# XMICRO-BP8.net
KiCad netlist of a schematic drawn in EAGLE
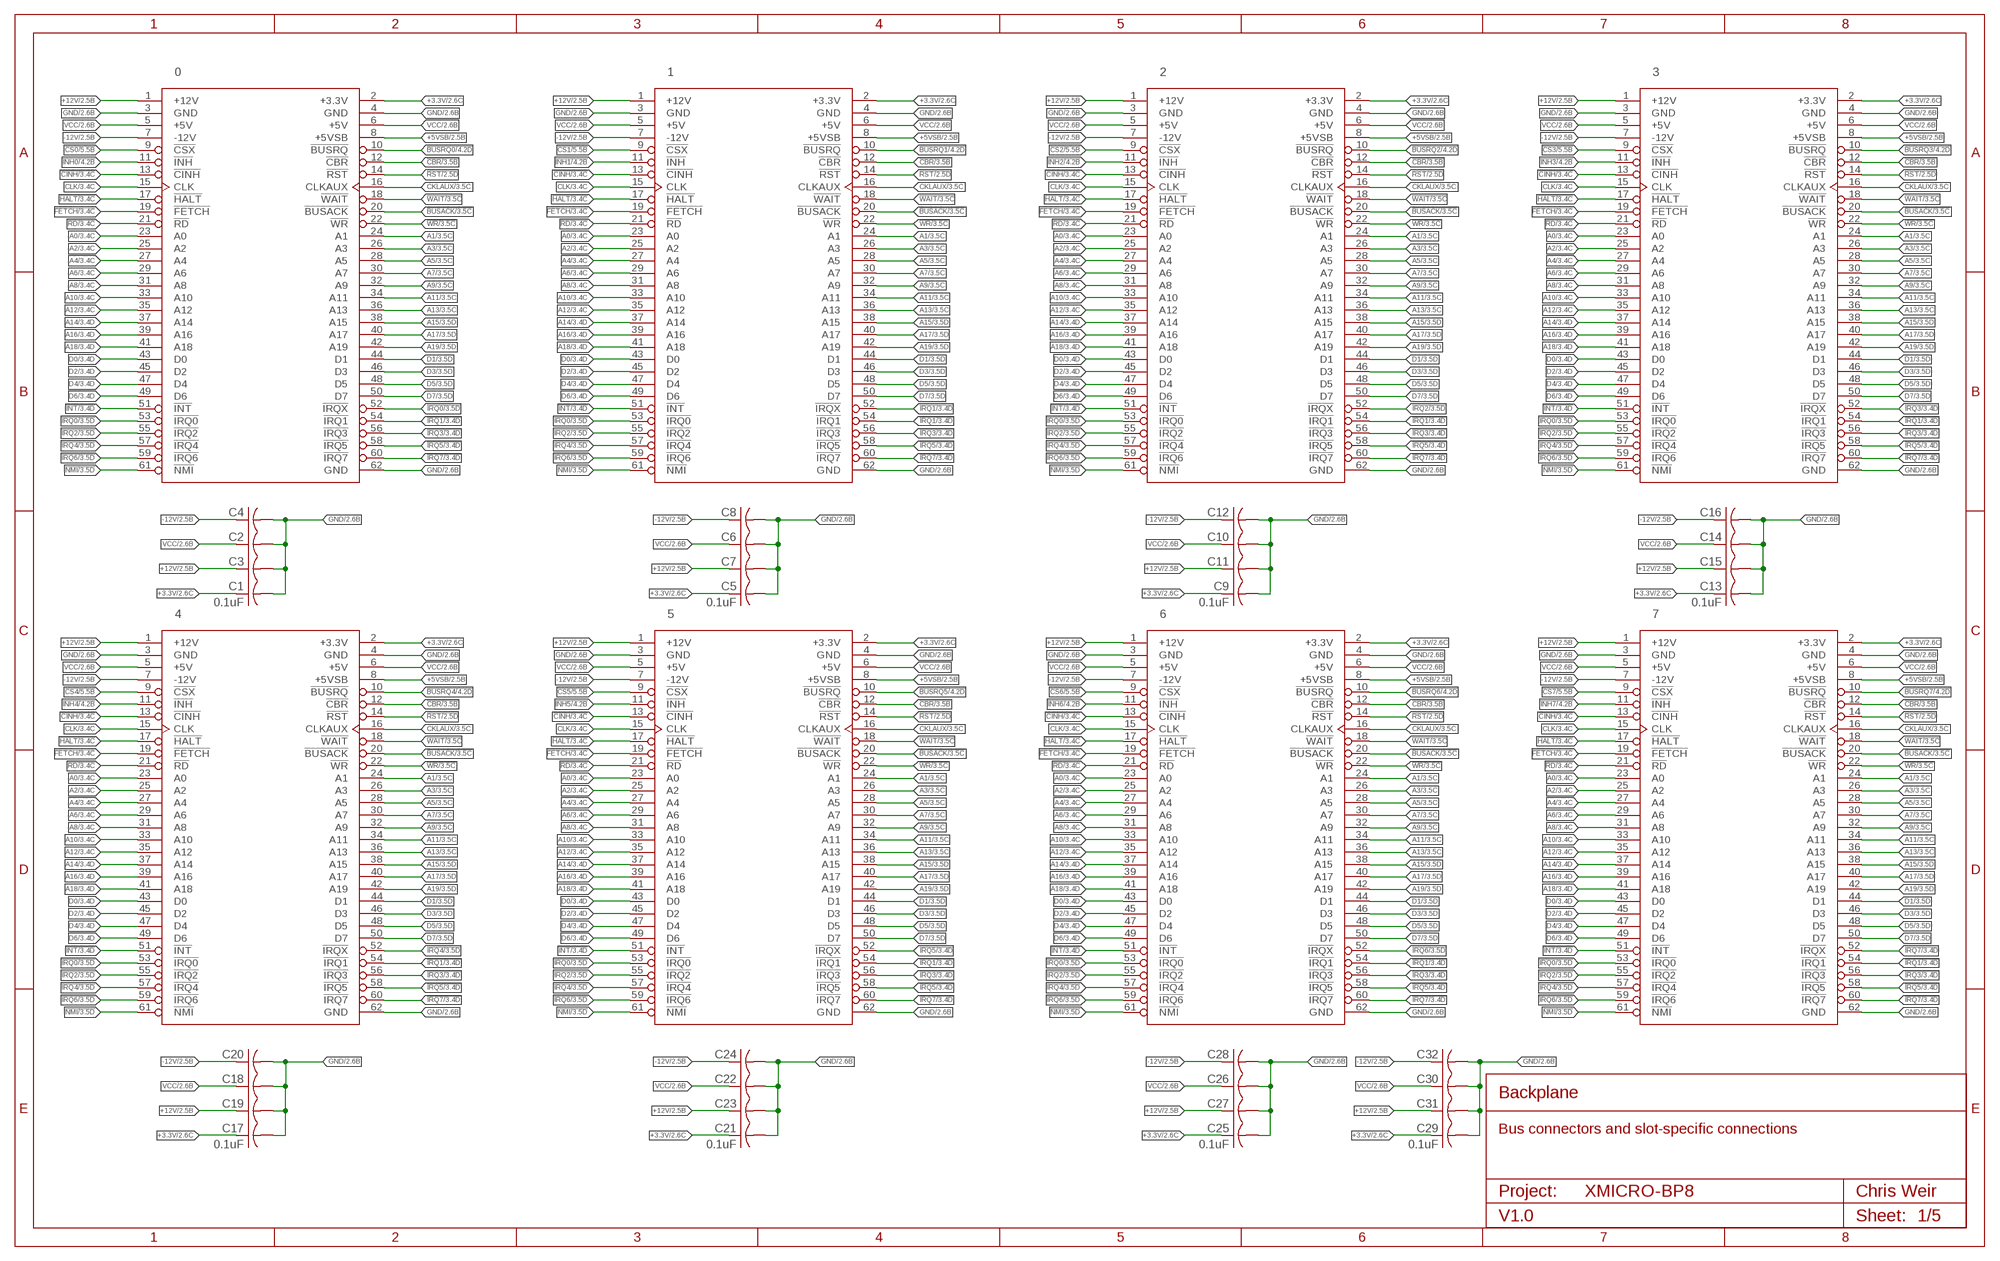
[diagram p0: schematic, sheet 1]
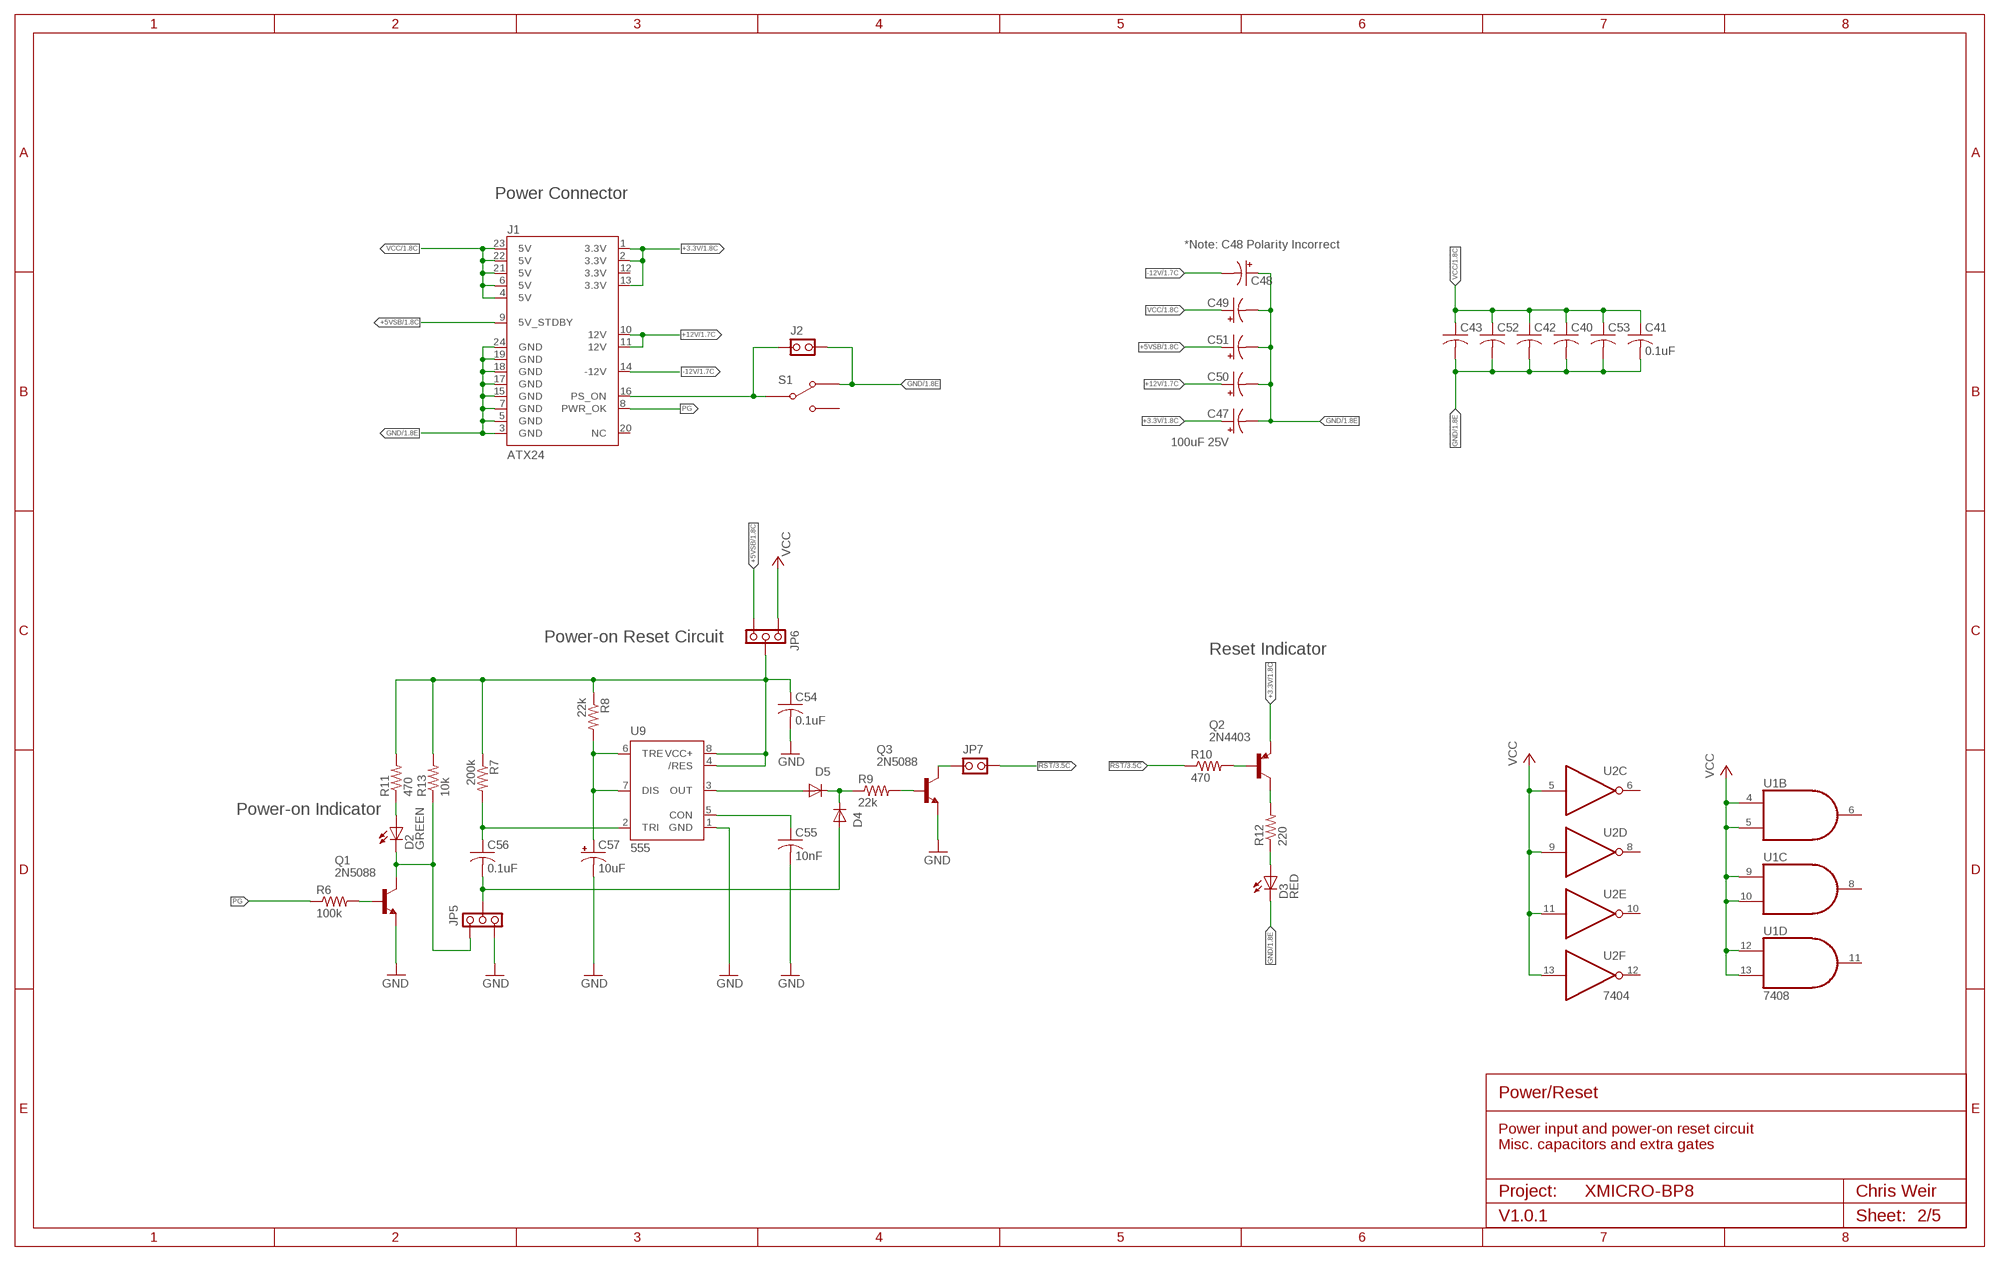
[diagram p1: schematic, sheet 2]
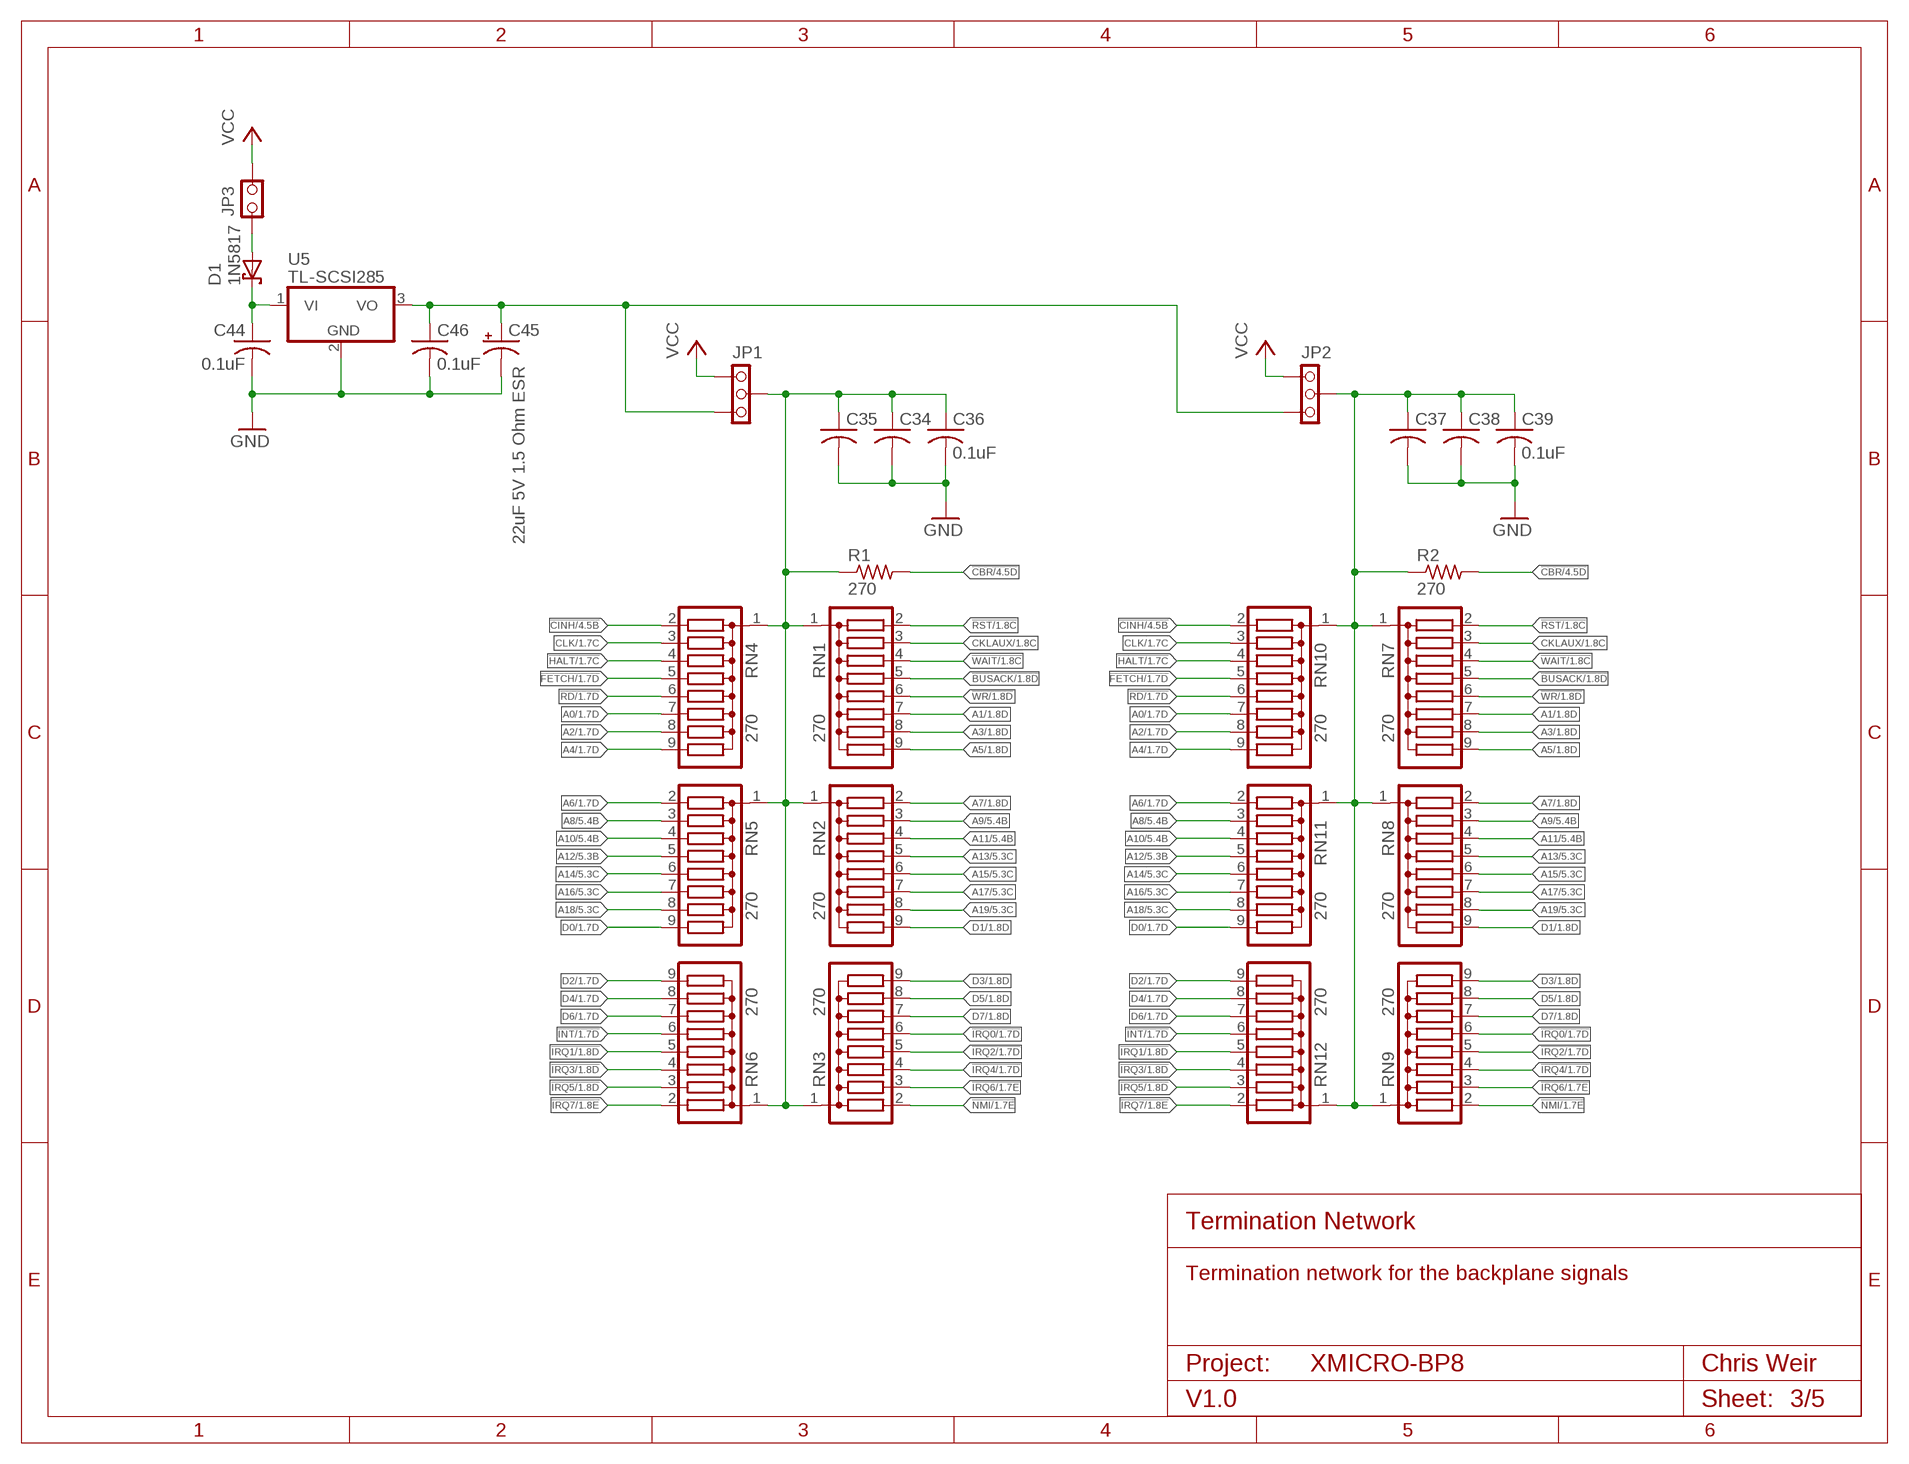
[diagram p2: schematic, sheet 3]
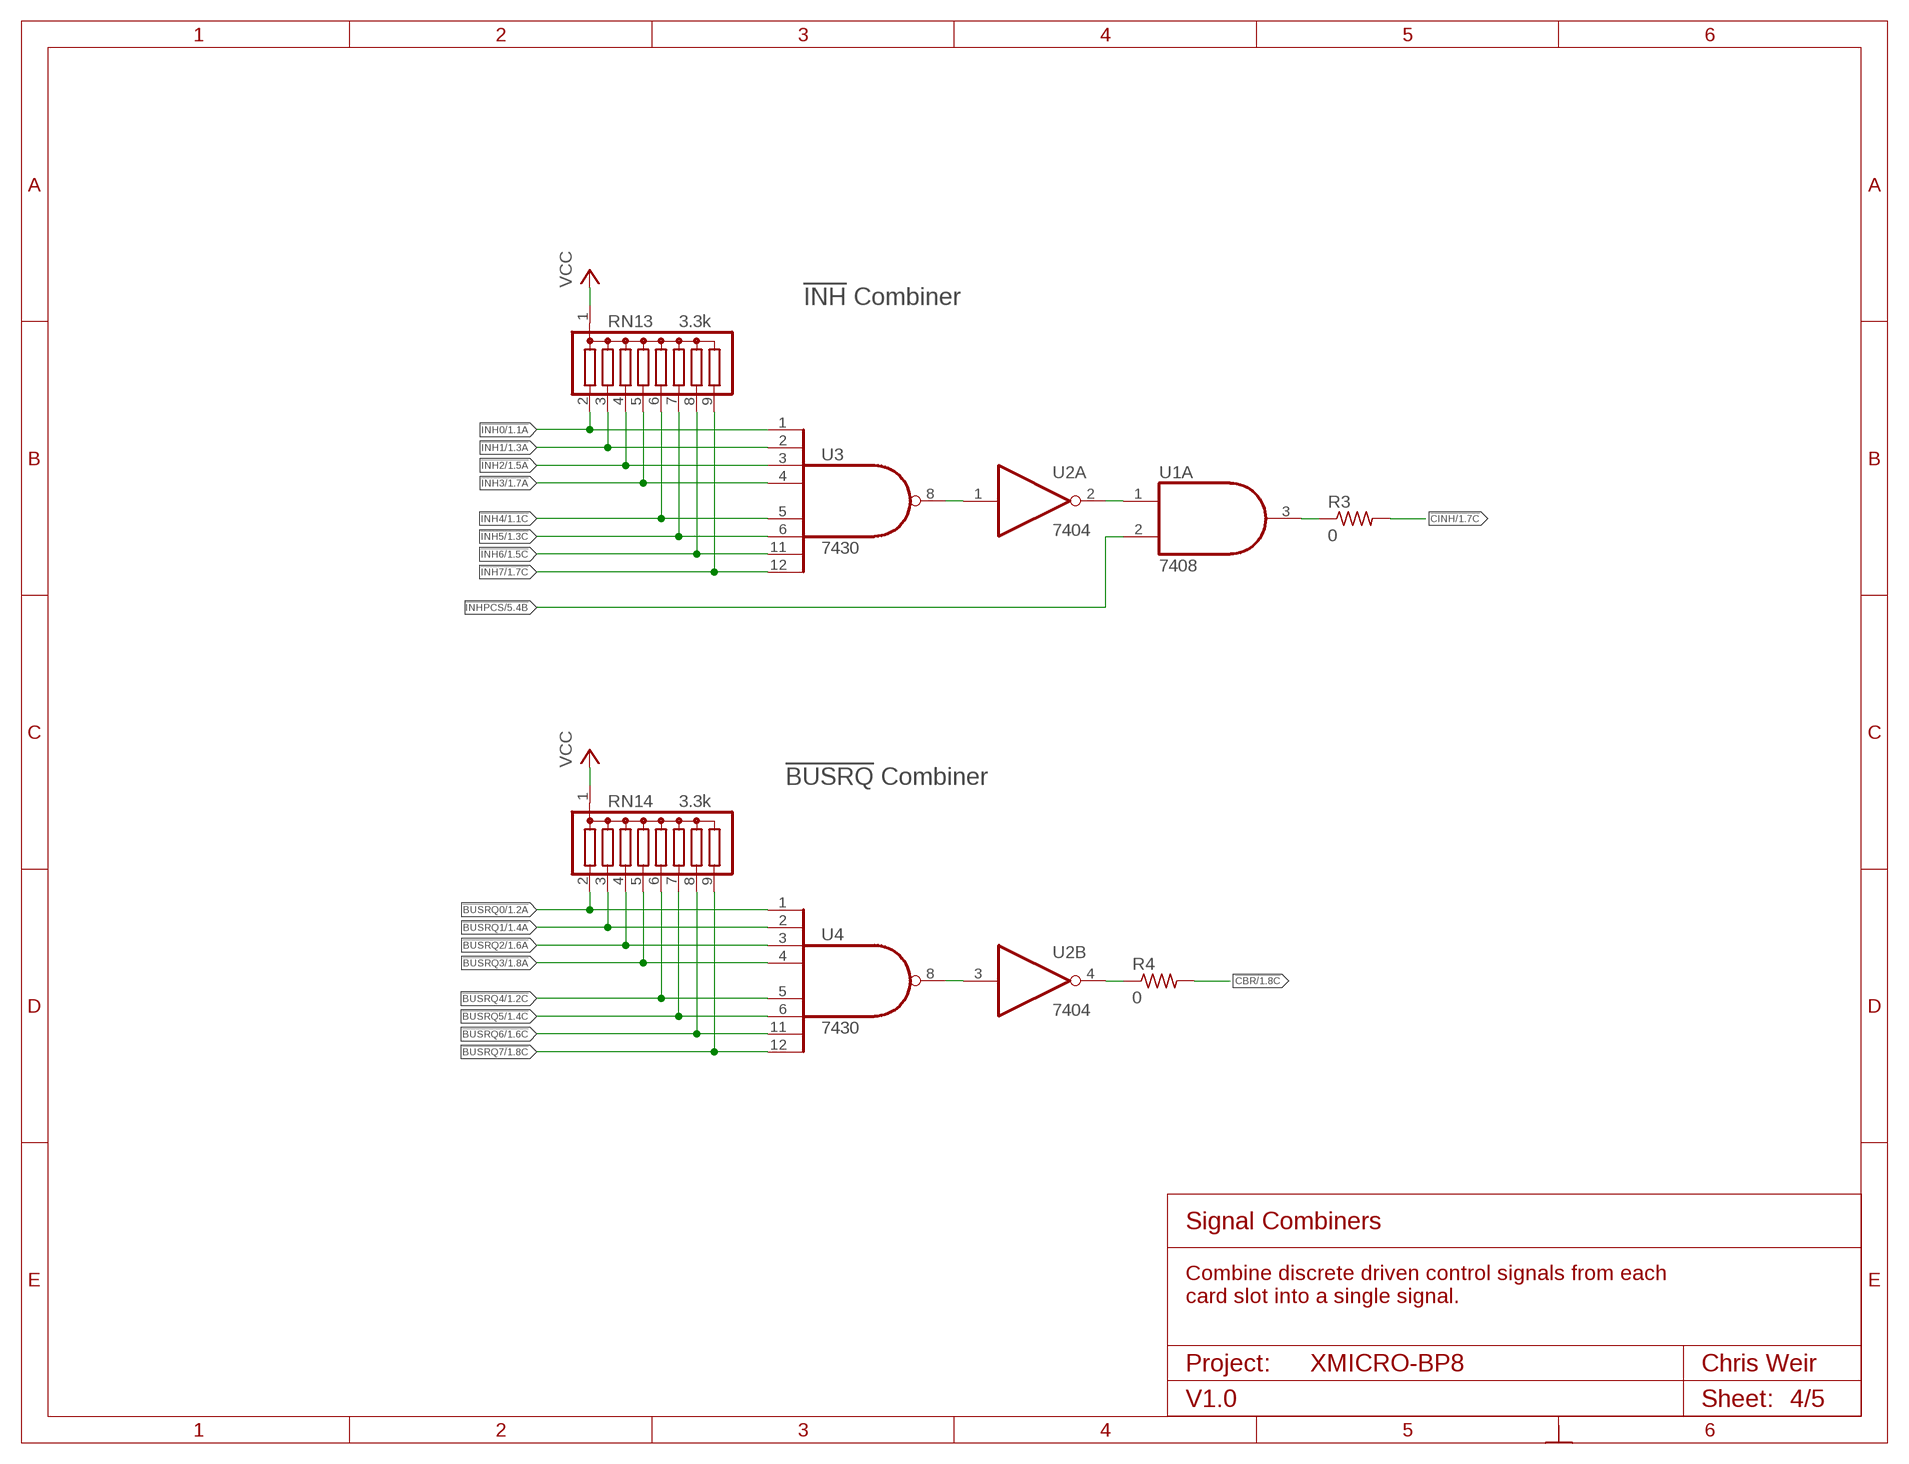
[diagram p3: schematic, sheet 4]
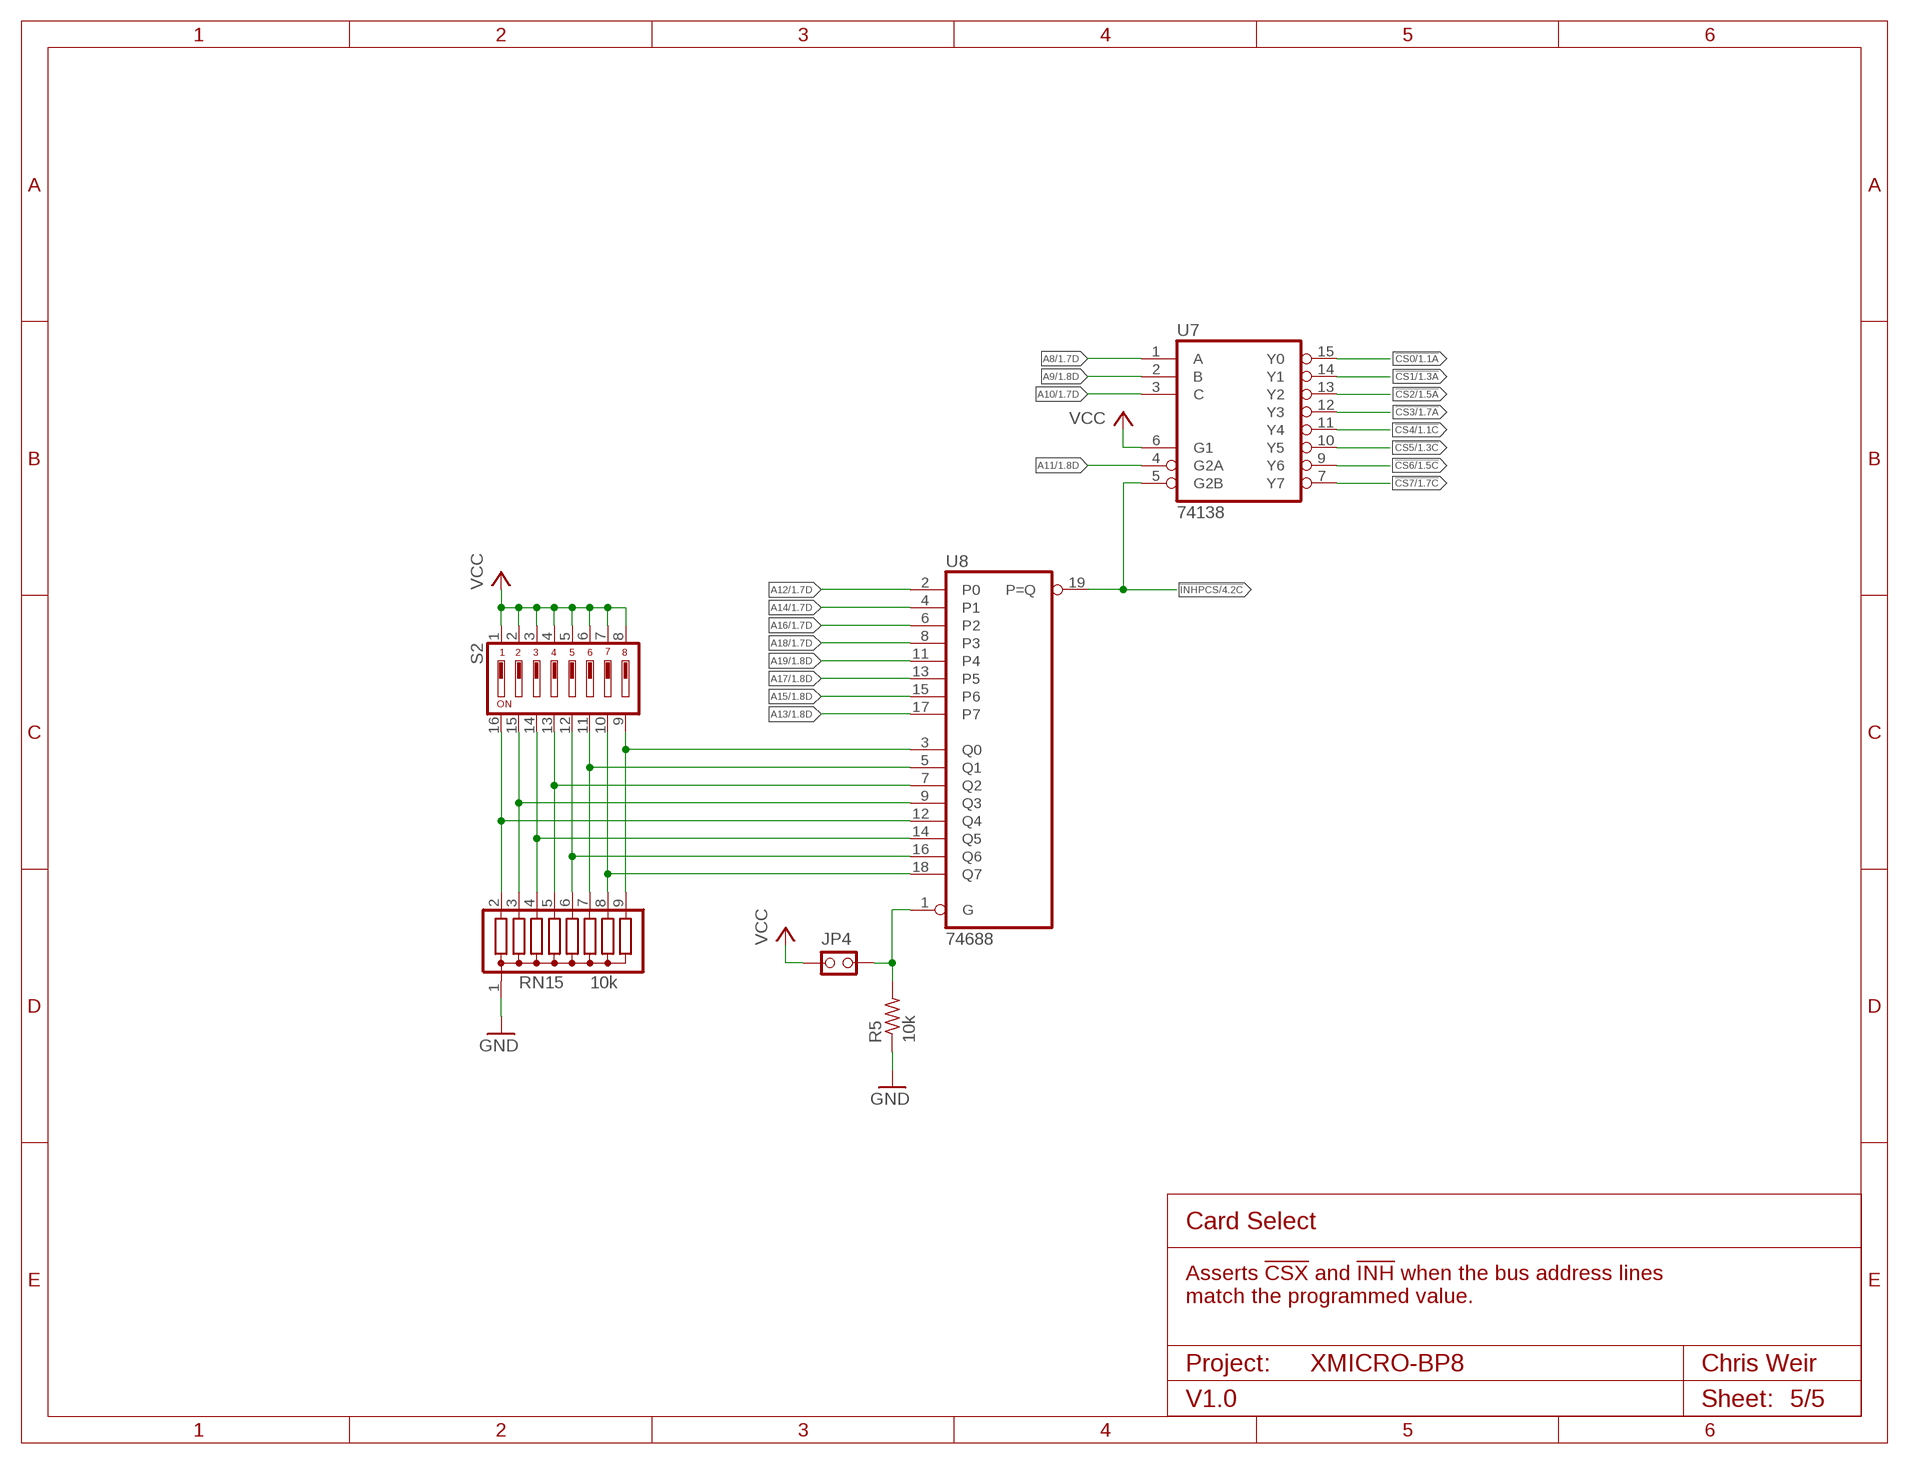
[diagram p4: schematic, sheet 5]

(export (version "E")
  (design (tool "Eeschema 10.0.6"))
  (components
    (comp (ref "C34")
      (value "0.1uF")
      (footprint "eagle-import:C025-024X044")
      (libsource (lib "eagle-import") (part "C-US025-024X044"))
    )
    (comp (ref "C35")
      (value "0.1uF")
      (footprint "eagle-import:C025-024X044")
      (libsource (lib "eagle-import") (part "C-US025-024X044"))
    )
    (comp (ref "C36")
      (value "0.1uF")
      (footprint "eagle-import:C025-024X044")
      (libsource (lib "eagle-import") (part "C-US025-024X044"))
    )
    (comp (ref "C37")
      (value "0.1uF")
      (footprint "eagle-import:C025-024X044")
      (libsource (lib "eagle-import") (part "C-US025-024X044"))
    )
    (comp (ref "C38")
      (value "0.1uF")
      (footprint "eagle-import:C025-024X044")
      (libsource (lib "eagle-import") (part "C-US025-024X044"))
    )
    (comp (ref "C39")
      (value "0.1uF")
      (footprint "eagle-import:C025-024X044")
      (libsource (lib "eagle-import") (part "C-US025-024X044"))
    )
    (comp (ref "C44")
      (value "0.1uF")
      (footprint "eagle-import:C025-024X044")
      (libsource (lib "eagle-import") (part "C-US025-024X044"))
    )
    (comp (ref "C45")
      (value "22uF 5V 1.5 Ohm ESR")
      (footprint "eagle-import:E2,5-7")
      (libsource (lib "eagle-import") (part "CPOL-USE2.5-7"))
    )
    (comp (ref "C46")
      (value "0.1uF")
      (footprint "eagle-import:C050-024X044")
      (libsource (lib "eagle-import") (part "C-US050-024X044"))
    )
    (comp (ref "D1")
      (value "1N5817")
      (footprint "eagle-import:DO41-7.6")
      (libsource (lib "eagle-import") (part "1N5817-B"))
    )
    (comp (ref "JP1")
      (value "PINHD1X3THRU")
      (footprint "eagle-import:1X03")
      (libsource (lib "eagle-import") (part "PINHD1X3THRU"))
    )
    (comp (ref "JP2")
      (value "PINHD1X3THRU")
      (footprint "eagle-import:1X03")
      (libsource (lib "eagle-import") (part "PINHD1X3THRU"))
    )
    (comp (ref "JP3")
      (value "PINHD-1X2THRU")
      (footprint "eagle-import:1X02")
      (libsource (lib "eagle-import") (part "PINHD-1X2THRU"))
    )
    (comp (ref "R1")
      (value "270")
      (footprint "eagle-import:0207_10")
      (libsource (lib "eagle-import") (part "R-US_0207/10"))
    )
    (comp (ref "R2")
      (value "270")
      (footprint "eagle-import:0207_10")
      (libsource (lib "eagle-import") (part "R-US_0207/10"))
    )
    (comp (ref "RN1")
      (value "270")
      (footprint "eagle-import:SIL9")
      (fields (field (name "OC_FARNELL") "unknown") (field (name "OC_NEWARK") "unknown"))
      (libsource (lib "eagle-import") (part "G08R"))
    )
    (comp (ref "RN2")
      (value "270")
      (footprint "eagle-import:SIL9")
      (fields (field (name "OC_FARNELL") "unknown") (field (name "OC_NEWARK") "unknown"))
      (libsource (lib "eagle-import") (part "G08R"))
    )
    (comp (ref "RN3")
      (value "270")
      (footprint "eagle-import:SIL9")
      (fields (field (name "OC_FARNELL") "unknown") (field (name "OC_NEWARK") "unknown"))
      (libsource (lib "eagle-import") (part "G08R"))
    )
    (comp (ref "RN4")
      (value "270")
      (footprint "eagle-import:SIL9")
      (fields (field (name "OC_FARNELL") "unknown") (field (name "OC_NEWARK") "unknown"))
      (libsource (lib "eagle-import") (part "G08R"))
    )
    (comp (ref "RN5")
      (value "270")
      (footprint "eagle-import:SIL9")
      (fields (field (name "OC_FARNELL") "unknown") (field (name "OC_NEWARK") "unknown"))
      (libsource (lib "eagle-import") (part "G08R"))
    )
    (comp (ref "RN6")
      (value "270")
      (footprint "eagle-import:SIL9")
      (fields (field (name "OC_FARNELL") "unknown") (field (name "OC_NEWARK") "unknown"))
      (libsource (lib "eagle-import") (part "G08R"))
    )
    (comp (ref "RN7")
      (value "270")
      (footprint "eagle-import:SIL9")
      (fields (field (name "OC_FARNELL") "unknown") (field (name "OC_NEWARK") "unknown"))
      (libsource (lib "eagle-import") (part "G08R"))
    )
    (comp (ref "RN8")
      (value "270")
      (footprint "eagle-import:SIL9")
      (fields (field (name "OC_FARNELL") "unknown") (field (name "OC_NEWARK") "unknown"))
      (libsource (lib "eagle-import") (part "G08R"))
    )
    (comp (ref "RN9")
      (value "270")
      (footprint "eagle-import:SIL9")
      (fields (field (name "OC_FARNELL") "unknown") (field (name "OC_NEWARK") "unknown"))
      (libsource (lib "eagle-import") (part "G08R"))
    )
    (comp (ref "RN10")
      (value "270")
      (footprint "eagle-import:SIL9")
      (fields (field (name "OC_FARNELL") "unknown") (field (name "OC_NEWARK") "unknown"))
      (libsource (lib "eagle-import") (part "G08R"))
    )
    (comp (ref "RN11")
      (value "270")
      (footprint "eagle-import:SIL9")
      (fields (field (name "OC_FARNELL") "unknown") (field (name "OC_NEWARK") "unknown"))
      (libsource (lib "eagle-import") (part "G08R"))
    )
    (comp (ref "RN12")
      (value "270")
      (footprint "eagle-import:SIL9")
      (fields (field (name "OC_FARNELL") "unknown") (field (name "OC_NEWARK") "unknown"))
      (libsource (lib "eagle-import") (part "G08R"))
    )
    (comp (ref "U5")
      (value "TL-SCSI285")
      (footprint "eagle-import:TO220H")
      (libsource (lib "eagle-import") (part "TL-SCSI285-TO220H"))
    )
    (comp (ref "JP4")
      (value "PINHD-1X2THRU")
      (footprint "eagle-import:1X02")
      (libsource (lib "eagle-import") (part "PINHD-1X2THRU"))
    )
    (comp (ref "R5")
      (value "10k")
      (footprint "eagle-import:0207_10")
      (libsource (lib "eagle-import") (part "R-US_0207/10"))
    )
    (comp (ref "RN15")
      (value "10k")
      (footprint "eagle-import:SIL9")
      (fields (field (name "OC_FARNELL") "unknown") (field (name "OC_NEWARK") "unknown"))
      (libsource (lib "eagle-import") (part "G08R"))
    )
    (comp (ref "S2")
      (value "SW-DIP08")
      (footprint "eagle-import:SW-DIP8")
      (libsource (lib "eagle-import") (part "SW-DIP08"))
    )
    (comp (ref "U7")
      (value "74138")
      (footprint "eagle-import:DIL16")
      (libsource (lib "eagle-import") (part "74138NLS"))
    )
    (comp (ref "U8")
      (value "74688")
      (footprint "eagle-import:DIL20")
      (libsource (lib "eagle-import") (part "74688NLS"))
    )
    (comp (ref "C40")
      (value "0.1uF")
      (footprint "eagle-import:C025-024X044")
      (libsource (lib "eagle-import") (part "C-US025-024X044"))
    )
    (comp (ref "C41")
      (value "0.1uF")
      (footprint "eagle-import:C025-024X044")
      (libsource (lib "eagle-import") (part "C-US025-024X044"))
    )
    (comp (ref "C42")
      (value "0.1uF")
      (footprint "eagle-import:C025-024X044")
      (libsource (lib "eagle-import") (part "C-US025-024X044"))
    )
    (comp (ref "C43")
      (value "0.1uF")
      (footprint "eagle-import:C025-024X044")
      (libsource (lib "eagle-import") (part "C-US025-024X044"))
    )
    (comp (ref "C47")
      (value "100uF 25V")
      (footprint "eagle-import:C-10-5")
      (libsource (lib "eagle-import") (part "CPOL-US-10-5"))
    )
    (comp (ref "C48")
      (value "220uF 10V")
      (footprint "eagle-import:C-10-5")
      (libsource (lib "eagle-import") (part "CPOL-US-10-5"))
    )
    (comp (ref "C49")
      (value "220uF 10V")
      (footprint "eagle-import:C-10-5")
      (libsource (lib "eagle-import") (part "CPOL-US-10-5"))
    )
    (comp (ref "C50")
      (value "100uF 25V")
      (footprint "eagle-import:C-10-5")
      (libsource (lib "eagle-import") (part "CPOL-US-10-5"))
    )
    (comp (ref "C51")
      (value "220uF 10V")
      (footprint "eagle-import:C-10-5")
      (libsource (lib "eagle-import") (part "CPOL-US-10-5"))
    )
    (comp (ref "C52")
      (value "0.1uF")
      (footprint "eagle-import:C025-024X044")
      (libsource (lib "eagle-import") (part "C-US025-024X044"))
    )
    (comp (ref "C53")
      (value "0.1uF")
      (footprint "eagle-import:C025-024X044")
      (libsource (lib "eagle-import") (part "C-US025-024X044"))
    )
    (comp (ref "C54")
      (value "0.1uF")
      (footprint "eagle-import:C025-024X044")
      (libsource (lib "eagle-import") (part "C-US025-024X044"))
    )
    (comp (ref "C55")
      (value "10nF")
      (footprint "eagle-import:C025-024X044")
      (libsource (lib "eagle-import") (part "C-US025-024X044"))
    )
    (comp (ref "C56")
      (value "0.1uF")
      (footprint "eagle-import:C025-024X044")
      (libsource (lib "eagle-import") (part "C-US025-024X044"))
    )
    (comp (ref "C57")
      (value "10uF")
      (footprint "eagle-import:E2,5-7")
      (libsource (lib "eagle-import") (part "CPOL-USE2.5-7"))
    )
    (comp (ref "D2")
      (value "GREEN")
      (footprint "eagle-import:LED5MM")
      (libsource (lib "eagle-import") (part "LED5MM"))
    )
    (comp (ref "D3")
      (value "RED")
      (footprint "eagle-import:LED5MM")
      (libsource (lib "eagle-import") (part "LED5MM"))
    )
    (comp (ref "D4")
      (value "1N4148DO35-7")
      (footprint "eagle-import:DO35-7")
      (libsource (lib "eagle-import") (part "1N4148DO35-7"))
    )
    (comp (ref "D5")
      (value "1N4148DO35-7")
      (footprint "eagle-import:DO35-7")
      (libsource (lib "eagle-import") (part "1N4148DO35-7"))
    )
    (comp (ref "J1")
      (value "ATX24")
      (footprint "eagle-import:ATX24")
      (libsource (lib "eagle-import") (part "ATX24"))
    )
    (comp (ref "J2")
      (value "PINHD-1X2THRU")
      (footprint "eagle-import:1X02")
      (libsource (lib "eagle-import") (part "PINHD-1X2THRU"))
    )
    (comp (ref "JP5")
      (value "PINHD1X3THRU")
      (footprint "eagle-import:1X03")
      (libsource (lib "eagle-import") (part "PINHD1X3THRU"))
    )
    (comp (ref "JP6")
      (value "PINHD1X3THRU")
      (footprint "eagle-import:1X03")
      (libsource (lib "eagle-import") (part "PINHD1X3THRU"))
    )
    (comp (ref "JP7")
      (value "PINHD-1X2THRU")
      (footprint "eagle-import:1X02")
      (libsource (lib "eagle-import") (part "PINHD-1X2THRU"))
    )
    (comp (ref "Q1")
      (value "2N5088")
      (footprint "eagle-import:TO92")
      (libsource (lib "eagle-import") (part "TRANSISTOR-NPN-2N5088"))
    )
    (comp (ref "Q2")
      (value "2N4403")
      (footprint "eagle-import:TO92")
      (libsource (lib "eagle-import") (part "TRANSISTOR-PNP-2N4403"))
    )
    (comp (ref "Q3")
      (value "2N5088")
      (footprint "eagle-import:TO92")
      (libsource (lib "eagle-import") (part "TRANSISTOR-NPN-2N5088"))
    )
    (comp (ref "R6")
      (value "100k")
      (footprint "eagle-import:0207_10")
      (libsource (lib "eagle-import") (part "R-US_0207/10"))
    )
    (comp (ref "R7")
      (value "200k")
      (footprint "eagle-import:0207_10")
      (libsource (lib "eagle-import") (part "R-US_0207/10"))
    )
    (comp (ref "R8")
      (value "22k")
      (footprint "eagle-import:0207_10")
      (libsource (lib "eagle-import") (part "R-US_0207/10"))
    )
    (comp (ref "R9")
      (value "22k")
      (footprint "eagle-import:0207_10")
      (libsource (lib "eagle-import") (part "R-US_0207/10"))
    )
    (comp (ref "R10")
      (value "470")
      (footprint "eagle-import:0207_10")
      (libsource (lib "eagle-import") (part "R-US_0207/10"))
    )
    (comp (ref "R11")
      (value "470")
      (footprint "eagle-import:0207_10")
      (libsource (lib "eagle-import") (part "R-US_0207/10"))
    )
    (comp (ref "R12")
      (value "220")
      (footprint "eagle-import:0207_10")
      (libsource (lib "eagle-import") (part "R-US_0207/10"))
    )
    (comp (ref "R13")
      (value "10k")
      (footprint "eagle-import:0207_10")
      (libsource (lib "eagle-import") (part "R-US_0207/10"))
    )
    (comp (ref "S1")
      (value "SPDTT411013")
      (footprint "eagle-import:T411013")
      (libsource (lib "eagle-import") (part "SPDTT411013"))
    )
    (comp (ref "U1")
      (value "7408")
      (footprint "eagle-import:DIL14")
      (libsource (lib "eagle-import") (part "7408NLS"))
    )
    (comp (ref "U2")
      (value "7404")
      (footprint "eagle-import:DIL14")
      (libsource (lib "eagle-import") (part "7404NLS"))
    )
    (comp (ref "U9")
      (value "555")
      (footprint "eagle-import:DIL-08")
      (fields (field (name "MF") "Arrow Electronics") (field (name "MPN") "NE555N"))
      (libsource (lib "eagle-import") (part "NE555"))
    )
    (comp (ref "0")
      (value "XMICRO-BUS-PHYSICAL-EDGE62F")
      (footprint "eagle-import:EDGE62F")
      (libsource (lib "eagle-import") (part "XMICRO-BUS-PHYSICAL-EDGE62F"))
    )
    (comp (ref "1")
      (value "XMICRO-BUS-PHYSICAL-EDGE62F")
      (footprint "eagle-import:EDGE62F")
      (libsource (lib "eagle-import") (part "XMICRO-BUS-PHYSICAL-EDGE62F"))
    )
    (comp (ref "2")
      (value "XMICRO-BUS-PHYSICAL-EDGE62F")
      (footprint "eagle-import:EDGE62F")
      (libsource (lib "eagle-import") (part "XMICRO-BUS-PHYSICAL-EDGE62F"))
    )
    (comp (ref "3")
      (value "XMICRO-BUS-PHYSICAL-EDGE62F")
      (footprint "eagle-import:EDGE62F")
      (libsource (lib "eagle-import") (part "XMICRO-BUS-PHYSICAL-EDGE62F"))
    )
    (comp (ref "4")
      (value "XMICRO-BUS-PHYSICAL-EDGE62F")
      (footprint "eagle-import:EDGE62F")
      (libsource (lib "eagle-import") (part "XMICRO-BUS-PHYSICAL-EDGE62F"))
    )
    (comp (ref "5")
      (value "XMICRO-BUS-PHYSICAL-EDGE62F")
      (footprint "eagle-import:EDGE62F")
      (libsource (lib "eagle-import") (part "XMICRO-BUS-PHYSICAL-EDGE62F"))
    )
    (comp (ref "6")
      (value "XMICRO-BUS-PHYSICAL-EDGE62F")
      (footprint "eagle-import:EDGE62F")
      (libsource (lib "eagle-import") (part "XMICRO-BUS-PHYSICAL-EDGE62F"))
    )
    (comp (ref "7")
      (value "XMICRO-BUS-PHYSICAL-EDGE62F")
      (footprint "eagle-import:EDGE62F")
      (libsource (lib "eagle-import") (part "XMICRO-BUS-PHYSICAL-EDGE62F"))
    )
    (comp (ref "C1")
      (value "0.1uF")
      (footprint "eagle-import:C025-024X044")
      (libsource (lib "eagle-import") (part "C-US025-024X044"))
    )
    (comp (ref "C2")
      (value "0.1uF")
      (footprint "eagle-import:C025-024X044")
      (libsource (lib "eagle-import") (part "C-US025-024X044"))
    )
    (comp (ref "C3")
      (value "0.1uF")
      (footprint "eagle-import:C025-024X044")
      (libsource (lib "eagle-import") (part "C-US025-024X044"))
    )
    (comp (ref "C4")
      (value "0.1uF")
      (footprint "eagle-import:C050-024X044")
      (libsource (lib "eagle-import") (part "C-US050-024X044"))
    )
    (comp (ref "C5")
      (value "0.1uF")
      (footprint "eagle-import:C025-024X044")
      (libsource (lib "eagle-import") (part "C-US025-024X044"))
    )
    (comp (ref "C6")
      (value "0.1uF")
      (footprint "eagle-import:C025-024X044")
      (libsource (lib "eagle-import") (part "C-US025-024X044"))
    )
    (comp (ref "C7")
      (value "0.1uF")
      (footprint "eagle-import:C025-024X044")
      (libsource (lib "eagle-import") (part "C-US025-024X044"))
    )
    (comp (ref "C8")
      (value "0.1uF")
      (footprint "eagle-import:C050-024X044")
      (libsource (lib "eagle-import") (part "C-US050-024X044"))
    )
    (comp (ref "C9")
      (value "0.1uF")
      (footprint "eagle-import:C025-024X044")
      (libsource (lib "eagle-import") (part "C-US025-024X044"))
    )
    (comp (ref "C10")
      (value "0.1uF")
      (footprint "eagle-import:C025-024X044")
      (libsource (lib "eagle-import") (part "C-US025-024X044"))
    )
    (comp (ref "C11")
      (value "0.1uF")
      (footprint "eagle-import:C025-024X044")
      (libsource (lib "eagle-import") (part "C-US025-024X044"))
    )
    (comp (ref "C12")
      (value "0.1uF")
      (footprint "eagle-import:C050-024X044")
      (libsource (lib "eagle-import") (part "C-US050-024X044"))
    )
    (comp (ref "C13")
      (value "0.1uF")
      (footprint "eagle-import:C025-024X044")
      (libsource (lib "eagle-import") (part "C-US025-024X044"))
    )
    (comp (ref "C14")
      (value "0.1uF")
      (footprint "eagle-import:C025-024X044")
      (libsource (lib "eagle-import") (part "C-US025-024X044"))
    )
    (comp (ref "C15")
      (value "0.1uF")
      (footprint "eagle-import:C025-024X044")
      (libsource (lib "eagle-import") (part "C-US025-024X044"))
    )
    (comp (ref "C16")
      (value "0.1uF")
      (footprint "eagle-import:C050-024X044")
      (libsource (lib "eagle-import") (part "C-US050-024X044"))
    )
    (comp (ref "C17")
      (value "0.1uF")
      (footprint "eagle-import:C025-024X044")
      (libsource (lib "eagle-import") (part "C-US025-024X044"))
    )
    (comp (ref "C18")
      (value "0.1uF")
      (footprint "eagle-import:C025-024X044")
      (libsource (lib "eagle-import") (part "C-US025-024X044"))
    )
    (comp (ref "C19")
      (value "0.1uF")
      (footprint "eagle-import:C025-024X044")
      (libsource (lib "eagle-import") (part "C-US025-024X044"))
    )
    (comp (ref "C20")
      (value "0.1uF")
      (footprint "eagle-import:C050-024X044")
      (libsource (lib "eagle-import") (part "C-US050-024X044"))
    )
    (comp (ref "C21")
      (value "0.1uF")
      (footprint "eagle-import:C025-024X044")
      (libsource (lib "eagle-import") (part "C-US025-024X044"))
    )
    (comp (ref "C22")
      (value "0.1uF")
      (footprint "eagle-import:C025-024X044")
      (libsource (lib "eagle-import") (part "C-US025-024X044"))
    )
    (comp (ref "C23")
      (value "0.1uF")
      (footprint "eagle-import:C025-024X044")
      (libsource (lib "eagle-import") (part "C-US025-024X044"))
    )
    (comp (ref "C24")
      (value "0.1uF")
      (footprint "eagle-import:C050-024X044")
      (libsource (lib "eagle-import") (part "C-US050-024X044"))
    )
    (comp (ref "C25")
      (value "0.1uF")
      (footprint "eagle-import:C025-024X044")
      (libsource (lib "eagle-import") (part "C-US025-024X044"))
    )
    (comp (ref "C26")
      (value "0.1uF")
      (footprint "eagle-import:C025-024X044")
      (libsource (lib "eagle-import") (part "C-US025-024X044"))
    )
    (comp (ref "C27")
      (value "0.1uF")
      (footprint "eagle-import:C025-024X044")
      (libsource (lib "eagle-import") (part "C-US025-024X044"))
    )
    (comp (ref "C28")
      (value "0.1uF")
      (footprint "eagle-import:C050-024X044")
      (libsource (lib "eagle-import") (part "C-US050-024X044"))
    )
    (comp (ref "C29")
      (value "0.1uF")
      (footprint "eagle-import:C025-024X044")
      (libsource (lib "eagle-import") (part "C-US025-024X044"))
    )
    (comp (ref "C30")
      (value "0.1uF")
      (footprint "eagle-import:C025-024X044")
      (libsource (lib "eagle-import") (part "C-US025-024X044"))
    )
    (comp (ref "C31")
      (value "0.1uF")
      (footprint "eagle-import:C025-024X044")
      (libsource (lib "eagle-import") (part "C-US025-024X044"))
    )
    (comp (ref "C32")
      (value "0.1uF")
      (footprint "eagle-import:C025-024X044")
      (libsource (lib "eagle-import") (part "C-US025-024X044"))
    )
    (comp (ref "R3")
      (value "0")
      (footprint "eagle-import:0207_10")
      (libsource (lib "eagle-import") (part "R-US_0207/10"))
    )
    (comp (ref "R4")
      (value "0")
      (footprint "eagle-import:0207_10")
      (libsource (lib "eagle-import") (part "R-US_0207/10"))
    )
    (comp (ref "RN13")
      (value "3.3k")
      (footprint "eagle-import:SIL9")
      (fields (field (name "OC_FARNELL") "unknown") (field (name "OC_NEWARK") "unknown"))
      (libsource (lib "eagle-import") (part "G08R"))
    )
    (comp (ref "RN14")
      (value "3.3k")
      (footprint "eagle-import:SIL9")
      (fields (field (name "OC_FARNELL") "unknown") (field (name "OC_NEWARK") "unknown"))
      (libsource (lib "eagle-import") (part "G08R"))
    )
    (comp (ref "U3")
      (value "7430")
      (footprint "eagle-import:DIL14")
      (libsource (lib "eagle-import") (part "7430NLS"))
    )
    (comp (ref "U4")
      (value "7430")
      (footprint "eagle-import:DIL14")
      (libsource (lib "eagle-import") (part "7430NLS"))
    )
  )
  (nets
    (net (code "1") (name "+3.3V") (class "Default")
      (node (ref "0") (pin "2") (pinfunction "+3.3V_2") (pintype "bidirectional"))
      (node (ref "1") (pin "2") (pinfunction "+3.3V_2") (pintype "bidirectional"))
      (node (ref "2") (pin "2") (pinfunction "+3.3V_2") (pintype "bidirectional"))
      (node (ref "3") (pin "2") (pinfunction "+3.3V_2") (pintype "bidirectional"))
      (node (ref "4") (pin "2") (pinfunction "+3.3V_2") (pintype "bidirectional"))
      (node (ref "5") (pin "2") (pinfunction "+3.3V_2") (pintype "bidirectional"))
      (node (ref "6") (pin "2") (pinfunction "+3.3V_2") (pintype "bidirectional"))
      (node (ref "7") (pin "2") (pinfunction "+3.3V_2") (pintype "bidirectional"))
      (node (ref "C1") (pin "1") (pinfunction "1_1") (pintype "passive"))
      (node (ref "C13") (pin "1") (pinfunction "1_1") (pintype "passive"))
      (node (ref "C17") (pin "1") (pinfunction "1_1") (pintype "passive"))
      (node (ref "C21") (pin "1") (pinfunction "1_1") (pintype "passive"))
      (node (ref "C25") (pin "1") (pinfunction "1_1") (pintype "passive"))
      (node (ref "C29") (pin "1") (pinfunction "1_1") (pintype "passive"))
      (node (ref "C47") (pin "+") (pinfunction "+_+") (pintype "passive"))
      (node (ref "C5") (pin "1") (pinfunction "1_1") (pintype "passive"))
      (node (ref "C9") (pin "1") (pinfunction "1_1") (pintype "passive"))
      (node (ref "J1") (pin "1") (pinfunction "3.3V_1") (pintype "bidirectional"))
      (node (ref "J1") (pin "13") (pinfunction "3.3V_13") (pintype "bidirectional"))
      (node (ref "J1") (pin "2") (pinfunction "3.3V_2") (pintype "bidirectional"))
      (node (ref "Q2") (pin "1") (pinfunction "E_1") (pintype "passive"))
    )
    (net (code "2") (name "+5VSB") (class "Default")
      (node (ref "0") (pin "8") (pinfunction "+5VSB_8") (pintype "bidirectional"))
      (node (ref "1") (pin "8") (pinfunction "+5VSB_8") (pintype "bidirectional"))
      (node (ref "2") (pin "8") (pinfunction "+5VSB_8") (pintype "bidirectional"))
      (node (ref "3") (pin "8") (pinfunction "+5VSB_8") (pintype "bidirectional"))
      (node (ref "4") (pin "8") (pinfunction "+5VSB_8") (pintype "bidirectional"))
      (node (ref "5") (pin "8") (pinfunction "+5VSB_8") (pintype "bidirectional"))
      (node (ref "6") (pin "8") (pinfunction "+5VSB_8") (pintype "bidirectional"))
      (node (ref "7") (pin "8") (pinfunction "+5VSB_8") (pintype "bidirectional"))
      (node (ref "C51") (pin "+") (pinfunction "+_+") (pintype "passive"))
      (node (ref "J1") (pin "9") (pinfunction "5V_STDBY_9") (pintype "bidirectional"))
      (node (ref "JP6") (pin "3") (pinfunction "3_3") (pintype "passive"))
    )
    (net (code "3") (name "+12V") (class "Default")
      (node (ref "0") (pin "1") (pinfunction "+12V_1") (pintype "bidirectional"))
      (node (ref "1") (pin "1") (pinfunction "+12V_1") (pintype "bidirectional"))
      (node (ref "2") (pin "1") (pinfunction "+12V_1") (pintype "bidirectional"))
      (node (ref "3") (pin "1") (pinfunction "+12V_1") (pintype "bidirectional"))
      (node (ref "4") (pin "1") (pinfunction "+12V_1") (pintype "bidirectional"))
      (node (ref "5") (pin "1") (pinfunction "+12V_1") (pintype "bidirectional"))
      (node (ref "6") (pin "1") (pinfunction "+12V_1") (pintype "bidirectional"))
      (node (ref "7") (pin "1") (pinfunction "+12V_1") (pintype "bidirectional"))
      (node (ref "C11") (pin "1") (pinfunction "1_1") (pintype "passive"))
      (node (ref "C15") (pin "1") (pinfunction "1_1") (pintype "passive"))
      (node (ref "C19") (pin "1") (pinfunction "1_1") (pintype "passive"))
      (node (ref "C23") (pin "1") (pinfunction "1_1") (pintype "passive"))
      (node (ref "C27") (pin "1") (pinfunction "1_1") (pintype "passive"))
      (node (ref "C3") (pin "1") (pinfunction "1_1") (pintype "passive"))
      (node (ref "C31") (pin "1") (pinfunction "1_1") (pintype "passive"))
      (node (ref "C50") (pin "+") (pinfunction "+_+") (pintype "passive"))
      (node (ref "C7") (pin "1") (pinfunction "1_1") (pintype "passive"))
      (node (ref "J1") (pin "10") (pinfunction "12V_10") (pintype "bidirectional"))
      (node (ref "J1") (pin "11") (pinfunction "12V_11") (pintype "bidirectional"))
    )
    (net (code "4") (name "-12V") (class "Default")
      (node (ref "0") (pin "7") (pinfunction "-12V_7") (pintype "bidirectional"))
      (node (ref "1") (pin "7") (pinfunction "-12V_7") (pintype "bidirectional"))
      (node (ref "2") (pin "7") (pinfunction "-12V_7") (pintype "bidirectional"))
      (node (ref "3") (pin "7") (pinfunction "-12V_7") (pintype "bidirectional"))
      (node (ref "4") (pin "7") (pinfunction "-12V_7") (pintype "bidirectional"))
      (node (ref "5") (pin "7") (pinfunction "-12V_7") (pintype "bidirectional"))
      (node (ref "6") (pin "7") (pinfunction "-12V_7") (pintype "bidirectional"))
      (node (ref "7") (pin "7") (pinfunction "-12V_7") (pintype "bidirectional"))
      (node (ref "C12") (pin "1") (pinfunction "1_1") (pintype "passive"))
      (node (ref "C16") (pin "1") (pinfunction "1_1") (pintype "passive"))
      (node (ref "C20") (pin "1") (pinfunction "1_1") (pintype "passive"))
      (node (ref "C24") (pin "1") (pinfunction "1_1") (pintype "passive"))
      (node (ref "C28") (pin "1") (pinfunction "1_1") (pintype "passive"))
      (node (ref "C32") (pin "1") (pinfunction "1_1") (pintype "passive"))
      (node (ref "C4") (pin "1") (pinfunction "1_1") (pintype "passive"))
      (node (ref "C48") (pin "-") (pinfunction "-_-") (pintype "passive"))
      (node (ref "C8") (pin "1") (pinfunction "1_1") (pintype "passive"))
      (node (ref "J1") (pin "14") (pinfunction "-12V_14") (pintype "bidirectional"))
    )
    (net (code "5") (name "A0") (class "Default")
      (node (ref "0") (pin "23") (pinfunction "A0_23") (pintype "bidirectional"))
      (node (ref "1") (pin "23") (pinfunction "A0_23") (pintype "bidirectional"))
      (node (ref "2") (pin "23") (pinfunction "A0_23") (pintype "bidirectional"))
      (node (ref "3") (pin "23") (pinfunction "A0_23") (pintype "bidirectional"))
      (node (ref "4") (pin "23") (pinfunction "A0_23") (pintype "bidirectional"))
      (node (ref "5") (pin "23") (pinfunction "A0_23") (pintype "bidirectional"))
      (node (ref "6") (pin "23") (pinfunction "A0_23") (pintype "bidirectional"))
      (node (ref "7") (pin "23") (pinfunction "A0_23") (pintype "bidirectional"))
      (node (ref "RN10") (pin "7") (pinfunction "7_7") (pintype "passive"))
      (node (ref "RN4") (pin "7") (pinfunction "7_7") (pintype "passive"))
    )
    (net (code "6") (name "A1") (class "Default")
      (node (ref "0") (pin "24") (pinfunction "A1_24") (pintype "bidirectional"))
      (node (ref "1") (pin "24") (pinfunction "A1_24") (pintype "bidirectional"))
      (node (ref "2") (pin "24") (pinfunction "A1_24") (pintype "bidirectional"))
      (node (ref "3") (pin "24") (pinfunction "A1_24") (pintype "bidirectional"))
      (node (ref "4") (pin "24") (pinfunction "A1_24") (pintype "bidirectional"))
      (node (ref "5") (pin "24") (pinfunction "A1_24") (pintype "bidirectional"))
      (node (ref "6") (pin "24") (pinfunction "A1_24") (pintype "bidirectional"))
      (node (ref "7") (pin "24") (pinfunction "A1_24") (pintype "bidirectional"))
      (node (ref "RN1") (pin "7") (pinfunction "7_7") (pintype "passive"))
      (node (ref "RN7") (pin "7") (pinfunction "7_7") (pintype "passive"))
    )
    (net (code "7") (name "A2") (class "Default")
      (node (ref "0") (pin "25") (pinfunction "A2_25") (pintype "bidirectional"))
      (node (ref "1") (pin "25") (pinfunction "A2_25") (pintype "bidirectional"))
      (node (ref "2") (pin "25") (pinfunction "A2_25") (pintype "bidirectional"))
      (node (ref "3") (pin "25") (pinfunction "A2_25") (pintype "bidirectional"))
      (node (ref "4") (pin "25") (pinfunction "A2_25") (pintype "bidirectional"))
      (node (ref "5") (pin "25") (pinfunction "A2_25") (pintype "bidirectional"))
      (node (ref "6") (pin "25") (pinfunction "A2_25") (pintype "bidirectional"))
      (node (ref "7") (pin "25") (pinfunction "A2_25") (pintype "bidirectional"))
      (node (ref "RN10") (pin "8") (pinfunction "8_8") (pintype "passive"))
      (node (ref "RN4") (pin "8") (pinfunction "8_8") (pintype "passive"))
    )
    (net (code "8") (name "A3") (class "Default")
      (node (ref "0") (pin "26") (pinfunction "A3_26") (pintype "bidirectional"))
      (node (ref "1") (pin "26") (pinfunction "A3_26") (pintype "bidirectional"))
      (node (ref "2") (pin "26") (pinfunction "A3_26") (pintype "bidirectional"))
      (node (ref "3") (pin "26") (pinfunction "A3_26") (pintype "bidirectional"))
      (node (ref "4") (pin "26") (pinfunction "A3_26") (pintype "bidirectional"))
      (node (ref "5") (pin "26") (pinfunction "A3_26") (pintype "bidirectional"))
      (node (ref "6") (pin "26") (pinfunction "A3_26") (pintype "bidirectional"))
      (node (ref "7") (pin "26") (pinfunction "A3_26") (pintype "bidirectional"))
      (node (ref "RN1") (pin "8") (pinfunction "8_8") (pintype "passive"))
      (node (ref "RN7") (pin "8") (pinfunction "8_8") (pintype "passive"))
    )
    (net (code "9") (name "A4") (class "Default")
      (node (ref "0") (pin "27") (pinfunction "A4_27") (pintype "bidirectional"))
      (node (ref "1") (pin "27") (pinfunction "A4_27") (pintype "bidirectional"))
      (node (ref "2") (pin "27") (pinfunction "A4_27") (pintype "bidirectional"))
      (node (ref "3") (pin "27") (pinfunction "A4_27") (pintype "bidirectional"))
      (node (ref "4") (pin "27") (pinfunction "A4_27") (pintype "bidirectional"))
      (node (ref "5") (pin "27") (pinfunction "A4_27") (pintype "bidirectional"))
      (node (ref "6") (pin "27") (pinfunction "A4_27") (pintype "bidirectional"))
      (node (ref "7") (pin "27") (pinfunction "A4_27") (pintype "bidirectional"))
      (node (ref "RN10") (pin "9") (pinfunction "9_9") (pintype "passive"))
      (node (ref "RN4") (pin "9") (pinfunction "9_9") (pintype "passive"))
    )
    (net (code "10") (name "A5") (class "Default")
      (node (ref "0") (pin "28") (pinfunction "A5_28") (pintype "bidirectional"))
      (node (ref "1") (pin "28") (pinfunction "A5_28") (pintype "bidirectional"))
      (node (ref "2") (pin "28") (pinfunction "A5_28") (pintype "bidirectional"))
      (node (ref "3") (pin "28") (pinfunction "A5_28") (pintype "bidirectional"))
      (node (ref "4") (pin "28") (pinfunction "A5_28") (pintype "bidirectional"))
      (node (ref "5") (pin "28") (pinfunction "A5_28") (pintype "bidirectional"))
      (node (ref "6") (pin "28") (pinfunction "A5_28") (pintype "bidirectional"))
      (node (ref "7") (pin "28") (pinfunction "A5_28") (pintype "bidirectional"))
      (node (ref "RN1") (pin "9") (pinfunction "9_9") (pintype "passive"))
      (node (ref "RN7") (pin "9") (pinfunction "9_9") (pintype "passive"))
    )
    (net (code "11") (name "A6") (class "Default")
      (node (ref "0") (pin "29") (pinfunction "A6_29") (pintype "bidirectional"))
      (node (ref "1") (pin "29") (pinfunction "A6_29") (pintype "bidirectional"))
      (node (ref "2") (pin "29") (pinfunction "A6_29") (pintype "bidirectional"))
      (node (ref "3") (pin "29") (pinfunction "A6_29") (pintype "bidirectional"))
      (node (ref "4") (pin "29") (pinfunction "A6_29") (pintype "bidirectional"))
      (node (ref "5") (pin "29") (pinfunction "A6_29") (pintype "bidirectional"))
      (node (ref "6") (pin "29") (pinfunction "A6_29") (pintype "bidirectional"))
      (node (ref "7") (pin "29") (pinfunction "A6_29") (pintype "bidirectional"))
      (node (ref "RN11") (pin "2") (pinfunction "2_2") (pintype "passive"))
      (node (ref "RN5") (pin "2") (pinfunction "2_2") (pintype "passive"))
    )
    (net (code "12") (name "A7") (class "Default")
      (node (ref "0") (pin "30") (pinfunction "A7_30") (pintype "bidirectional"))
      (node (ref "1") (pin "30") (pinfunction "A7_30") (pintype "bidirectional"))
      (node (ref "2") (pin "30") (pinfunction "A7_30") (pintype "bidirectional"))
      (node (ref "3") (pin "30") (pinfunction "A7_30") (pintype "bidirectional"))
      (node (ref "4") (pin "30") (pinfunction "A7_30") (pintype "bidirectional"))
      (node (ref "5") (pin "30") (pinfunction "A7_30") (pintype "bidirectional"))
      (node (ref "6") (pin "30") (pinfunction "A7_30") (pintype "bidirectional"))
      (node (ref "7") (pin "30") (pinfunction "A7_30") (pintype "bidirectional"))
      (node (ref "RN2") (pin "2") (pinfunction "2_2") (pintype "passive"))
      (node (ref "RN8") (pin "2") (pinfunction "2_2") (pintype "passive"))
    )
    (net (code "13") (name "A8") (class "Default")
      (node (ref "0") (pin "31") (pinfunction "A8_31") (pintype "bidirectional"))
      (node (ref "1") (pin "31") (pinfunction "A8_31") (pintype "bidirectional"))
      (node (ref "2") (pin "31") (pinfunction "A8_31") (pintype "bidirectional"))
      (node (ref "3") (pin "31") (pinfunction "A8_31") (pintype "bidirectional"))
      (node (ref "4") (pin "31") (pinfunction "A8_31") (pintype "bidirectional"))
      (node (ref "5") (pin "31") (pinfunction "A8_31") (pintype "bidirectional"))
      (node (ref "6") (pin "31") (pinfunction "A8_31") (pintype "bidirectional"))
      (node (ref "7") (pin "31") (pinfunction "A8_31") (pintype "bidirectional"))
      (node (ref "RN11") (pin "3") (pinfunction "3_3") (pintype "passive"))
      (node (ref "RN5") (pin "3") (pinfunction "3_3") (pintype "passive"))
      (node (ref "U7") (pin "1") (pinfunction "A_1") (pintype "input"))
    )
    (net (code "14") (name "A9") (class "Default")
      (node (ref "0") (pin "32") (pinfunction "A9_32") (pintype "bidirectional"))
      (node (ref "1") (pin "32") (pinfunction "A9_32") (pintype "bidirectional"))
      (node (ref "2") (pin "32") (pinfunction "A9_32") (pintype "bidirectional"))
      (node (ref "3") (pin "32") (pinfunction "A9_32") (pintype "bidirectional"))
      (node (ref "4") (pin "32") (pinfunction "A9_32") (pintype "bidirectional"))
      (node (ref "5") (pin "32") (pinfunction "A9_32") (pintype "bidirectional"))
      (node (ref "6") (pin "32") (pinfunction "A9_32") (pintype "bidirectional"))
      (node (ref "7") (pin "32") (pinfunction "A9_32") (pintype "bidirectional"))
      (node (ref "RN2") (pin "3") (pinfunction "3_3") (pintype "passive"))
      (node (ref "RN8") (pin "3") (pinfunction "3_3") (pintype "passive"))
      (node (ref "U7") (pin "2") (pinfunction "B_2") (pintype "input"))
    )
    (net (code "15") (name "A10") (class "Default")
      (node (ref "0") (pin "33") (pinfunction "A10_33") (pintype "bidirectional"))
      (node (ref "1") (pin "33") (pinfunction "A10_33") (pintype "bidirectional"))
      (node (ref "2") (pin "33") (pinfunction "A10_33") (pintype "bidirectional"))
      (node (ref "3") (pin "33") (pinfunction "A10_33") (pintype "bidirectional"))
      (node (ref "4") (pin "33") (pinfunction "A10_33") (pintype "bidirectional"))
      (node (ref "5") (pin "33") (pinfunction "A10_33") (pintype "bidirectional"))
      (node (ref "6") (pin "33") (pinfunction "A10_33") (pintype "bidirectional"))
      (node (ref "7") (pin "33") (pinfunction "A10_33") (pintype "bidirectional"))
      (node (ref "RN11") (pin "4") (pinfunction "4_4") (pintype "passive"))
      (node (ref "RN5") (pin "4") (pinfunction "4_4") (pintype "passive"))
      (node (ref "U7") (pin "3") (pinfunction "C_3") (pintype "input"))
    )
    (net (code "16") (name "A11") (class "Default")
      (node (ref "0") (pin "34") (pinfunction "A11_34") (pintype "bidirectional"))
      (node (ref "1") (pin "34") (pinfunction "A11_34") (pintype "bidirectional"))
      (node (ref "2") (pin "34") (pinfunction "A11_34") (pintype "bidirectional"))
      (node (ref "3") (pin "34") (pinfunction "A11_34") (pintype "bidirectional"))
      (node (ref "4") (pin "34") (pinfunction "A11_34") (pintype "bidirectional"))
      (node (ref "5") (pin "34") (pinfunction "A11_34") (pintype "bidirectional"))
      (node (ref "6") (pin "34") (pinfunction "A11_34") (pintype "bidirectional"))
      (node (ref "7") (pin "34") (pinfunction "A11_34") (pintype "bidirectional"))
      (node (ref "RN2") (pin "4") (pinfunction "4_4") (pintype "passive"))
      (node (ref "RN8") (pin "4") (pinfunction "4_4") (pintype "passive"))
      (node (ref "U7") (pin "4") (pinfunction "G2A_4") (pintype "input"))
    )
    (net (code "17") (name "A12") (class "Default")
      (node (ref "0") (pin "35") (pinfunction "A12_35") (pintype "bidirectional"))
      (node (ref "1") (pin "35") (pinfunction "A12_35") (pintype "bidirectional"))
      (node (ref "2") (pin "35") (pinfunction "A12_35") (pintype "bidirectional"))
      (node (ref "3") (pin "35") (pinfunction "A12_35") (pintype "bidirectional"))
      (node (ref "4") (pin "35") (pinfunction "A12_35") (pintype "bidirectional"))
      (node (ref "5") (pin "35") (pinfunction "A12_35") (pintype "bidirectional"))
      (node (ref "6") (pin "35") (pinfunction "A12_35") (pintype "bidirectional"))
      (node (ref "7") (pin "35") (pinfunction "A12_35") (pintype "bidirectional"))
      (node (ref "RN11") (pin "5") (pinfunction "5_5") (pintype "passive"))
      (node (ref "RN5") (pin "5") (pinfunction "5_5") (pintype "passive"))
      (node (ref "U8") (pin "2") (pinfunction "P0_2") (pintype "input"))
    )
    (net (code "18") (name "A13") (class "Default")
      (node (ref "0") (pin "36") (pinfunction "A13_36") (pintype "bidirectional"))
      (node (ref "1") (pin "36") (pinfunction "A13_36") (pintype "bidirectional"))
      (node (ref "2") (pin "36") (pinfunction "A13_36") (pintype "bidirectional"))
      (node (ref "3") (pin "36") (pinfunction "A13_36") (pintype "bidirectional"))
      (node (ref "4") (pin "36") (pinfunction "A13_36") (pintype "bidirectional"))
      (node (ref "5") (pin "36") (pinfunction "A13_36") (pintype "bidirectional"))
      (node (ref "6") (pin "36") (pinfunction "A13_36") (pintype "bidirectional"))
      (node (ref "7") (pin "36") (pinfunction "A13_36") (pintype "bidirectional"))
      (node (ref "RN2") (pin "5") (pinfunction "5_5") (pintype "passive"))
      (node (ref "RN8") (pin "5") (pinfunction "5_5") (pintype "passive"))
      (node (ref "U8") (pin "17") (pinfunction "P7_17") (pintype "input"))
    )
    (net (code "19") (name "A14") (class "Default")
      (node (ref "0") (pin "37") (pinfunction "A14_37") (pintype "bidirectional"))
      (node (ref "1") (pin "37") (pinfunction "A14_37") (pintype "bidirectional"))
      (node (ref "2") (pin "37") (pinfunction "A14_37") (pintype "bidirectional"))
      (node (ref "3") (pin "37") (pinfunction "A14_37") (pintype "bidirectional"))
      (node (ref "4") (pin "37") (pinfunction "A14_37") (pintype "bidirectional"))
      (node (ref "5") (pin "37") (pinfunction "A14_37") (pintype "bidirectional"))
      (node (ref "6") (pin "37") (pinfunction "A14_37") (pintype "bidirectional"))
      (node (ref "7") (pin "37") (pinfunction "A14_37") (pintype "bidirectional"))
      (node (ref "RN11") (pin "6") (pinfunction "6_6") (pintype "passive"))
      (node (ref "RN5") (pin "6") (pinfunction "6_6") (pintype "passive"))
      (node (ref "U8") (pin "4") (pinfunction "P1_4") (pintype "input"))
    )
    (net (code "20") (name "A15") (class "Default")
      (node (ref "0") (pin "38") (pinfunction "A15_38") (pintype "bidirectional"))
      (node (ref "1") (pin "38") (pinfunction "A15_38") (pintype "bidirectional"))
      (node (ref "2") (pin "38") (pinfunction "A15_38") (pintype "bidirectional"))
      (node (ref "3") (pin "38") (pinfunction "A15_38") (pintype "bidirectional"))
      (node (ref "4") (pin "38") (pinfunction "A15_38") (pintype "bidirectional"))
      (node (ref "5") (pin "38") (pinfunction "A15_38") (pintype "bidirectional"))
      (node (ref "6") (pin "38") (pinfunction "A15_38") (pintype "bidirectional"))
      (node (ref "7") (pin "38") (pinfunction "A15_38") (pintype "bidirectional"))
      (node (ref "RN2") (pin "6") (pinfunction "6_6") (pintype "passive"))
      (node (ref "RN8") (pin "6") (pinfunction "6_6") (pintype "passive"))
      (node (ref "U8") (pin "15") (pinfunction "P6_15") (pintype "input"))
    )
    (net (code "21") (name "A16") (class "Default")
      (node (ref "0") (pin "39") (pinfunction "A16_39") (pintype "bidirectional"))
      (node (ref "1") (pin "39") (pinfunction "A16_39") (pintype "bidirectional"))
      (node (ref "2") (pin "39") (pinfunction "A16_39") (pintype "bidirectional"))
      (node (ref "3") (pin "39") (pinfunction "A16_39") (pintype "bidirectional"))
      (node (ref "4") (pin "39") (pinfunction "A16_39") (pintype "bidirectional"))
      (node (ref "5") (pin "39") (pinfunction "A16_39") (pintype "bidirectional"))
      (node (ref "6") (pin "39") (pinfunction "A16_39") (pintype "bidirectional"))
      (node (ref "7") (pin "39") (pinfunction "A16_39") (pintype "bidirectional"))
      (node (ref "RN11") (pin "7") (pinfunction "7_7") (pintype "passive"))
      (node (ref "RN5") (pin "7") (pinfunction "7_7") (pintype "passive"))
      (node (ref "U8") (pin "6") (pinfunction "P2_6") (pintype "input"))
    )
    (net (code "22") (name "A17") (class "Default")
      (node (ref "0") (pin "40") (pinfunction "A17_40") (pintype "bidirectional"))
      (node (ref "1") (pin "40") (pinfunction "A17_40") (pintype "bidirectional"))
      (node (ref "2") (pin "40") (pinfunction "A17_40") (pintype "bidirectional"))
      (node (ref "3") (pin "40") (pinfunction "A17_40") (pintype "bidirectional"))
      (node (ref "4") (pin "40") (pinfunction "A17_40") (pintype "bidirectional"))
      (node (ref "5") (pin "40") (pinfunction "A17_40") (pintype "bidirectional"))
      (node (ref "6") (pin "40") (pinfunction "A17_40") (pintype "bidirectional"))
      (node (ref "7") (pin "40") (pinfunction "A17_40") (pintype "bidirectional"))
      (node (ref "RN2") (pin "7") (pinfunction "7_7") (pintype "passive"))
      (node (ref "RN8") (pin "7") (pinfunction "7_7") (pintype "passive"))
      (node (ref "U8") (pin "13") (pinfunction "P5_13") (pintype "input"))
    )
    (net (code "23") (name "A18") (class "Default")
      (node (ref "0") (pin "41") (pinfunction "A18_41") (pintype "bidirectional"))
      (node (ref "1") (pin "41") (pinfunction "A18_41") (pintype "bidirectional"))
      (node (ref "2") (pin "41") (pinfunction "A18_41") (pintype "bidirectional"))
      (node (ref "3") (pin "41") (pinfunction "A18_41") (pintype "bidirectional"))
      (node (ref "4") (pin "41") (pinfunction "A18_41") (pintype "bidirectional"))
      (node (ref "5") (pin "41") (pinfunction "A18_41") (pintype "bidirectional"))
      (node (ref "6") (pin "41") (pinfunction "A18_41") (pintype "bidirectional"))
      (node (ref "7") (pin "41") (pinfunction "A18_41") (pintype "bidirectional"))
      (node (ref "RN11") (pin "8") (pinfunction "8_8") (pintype "passive"))
      (node (ref "RN5") (pin "8") (pinfunction "8_8") (pintype "passive"))
      (node (ref "U8") (pin "8") (pinfunction "P3_8") (pintype "input"))
    )
    (net (code "24") (name "A19") (class "Default")
      (node (ref "0") (pin "42") (pinfunction "A19_42") (pintype "bidirectional"))
      (node (ref "1") (pin "42") (pinfunction "A19_42") (pintype "bidirectional"))
      (node (ref "2") (pin "42") (pinfunction "A19_42") (pintype "bidirectional"))
      (node (ref "3") (pin "42") (pinfunction "A19_42") (pintype "bidirectional"))
      (node (ref "4") (pin "42") (pinfunction "A19_42") (pintype "bidirectional"))
      (node (ref "5") (pin "42") (pinfunction "A19_42") (pintype "bidirectional"))
      (node (ref "6") (pin "42") (pinfunction "A19_42") (pintype "bidirectional"))
      (node (ref "7") (pin "42") (pinfunction "A19_42") (pintype "bidirectional"))
      (node (ref "RN2") (pin "8") (pinfunction "8_8") (pintype "passive"))
      (node (ref "RN8") (pin "8") (pinfunction "8_8") (pintype "passive"))
      (node (ref "U8") (pin "11") (pinfunction "P4_11") (pintype "input"))
    )
    (net (code "25") (name "CKLAUX") (class "Default")
      (node (ref "0") (pin "16") (pinfunction "CLKAUX_16") (pintype "bidirectional"))
      (node (ref "1") (pin "16") (pinfunction "CLKAUX_16") (pintype "bidirectional"))
      (node (ref "2") (pin "16") (pinfunction "CLKAUX_16") (pintype "bidirectional"))
      (node (ref "3") (pin "16") (pinfunction "CLKAUX_16") (pintype "bidirectional"))
      (node (ref "4") (pin "16") (pinfunction "CLKAUX_16") (pintype "bidirectional"))
      (node (ref "5") (pin "16") (pinfunction "CLKAUX_16") (pintype "bidirectional"))
      (node (ref "6") (pin "16") (pinfunction "CLKAUX_16") (pintype "bidirectional"))
      (node (ref "7") (pin "16") (pinfunction "CLKAUX_16") (pintype "bidirectional"))
      (node (ref "RN1") (pin "3") (pinfunction "3_3") (pintype "passive"))
      (node (ref "RN7") (pin "3") (pinfunction "3_3") (pintype "passive"))
    )
    (net (code "26") (name "CLK") (class "Default")
      (node (ref "0") (pin "15") (pinfunction "CLK_15") (pintype "bidirectional"))
      (node (ref "1") (pin "15") (pinfunction "CLK_15") (pintype "bidirectional"))
      (node (ref "2") (pin "15") (pinfunction "CLK_15") (pintype "bidirectional"))
      (node (ref "3") (pin "15") (pinfunction "CLK_15") (pintype "bidirectional"))
      (node (ref "4") (pin "15") (pinfunction "CLK_15") (pintype "bidirectional"))
      (node (ref "5") (pin "15") (pinfunction "CLK_15") (pintype "bidirectional"))
      (node (ref "6") (pin "15") (pinfunction "CLK_15") (pintype "bidirectional"))
      (node (ref "7") (pin "15") (pinfunction "CLK_15") (pintype "bidirectional"))
      (node (ref "RN10") (pin "3") (pinfunction "3_3") (pintype "passive"))
      (node (ref "RN4") (pin "3") (pinfunction "3_3") (pintype "passive"))
    )
    (net (code "27") (name "D0") (class "Default")
      (node (ref "0") (pin "43") (pinfunction "D0_43") (pintype "bidirectional"))
      (node (ref "1") (pin "43") (pinfunction "D0_43") (pintype "bidirectional"))
      (node (ref "2") (pin "43") (pinfunction "D0_43") (pintype "bidirectional"))
      (node (ref "3") (pin "43") (pinfunction "D0_43") (pintype "bidirectional"))
      (node (ref "4") (pin "43") (pinfunction "D0_43") (pintype "bidirectional"))
      (node (ref "5") (pin "43") (pinfunction "D0_43") (pintype "bidirectional"))
      (node (ref "6") (pin "43") (pinfunction "D0_43") (pintype "bidirectional"))
      (node (ref "7") (pin "43") (pinfunction "D0_43") (pintype "bidirectional"))
      (node (ref "RN11") (pin "9") (pinfunction "9_9") (pintype "passive"))
      (node (ref "RN5") (pin "9") (pinfunction "9_9") (pintype "passive"))
    )
    (net (code "28") (name "D1") (class "Default")
      (node (ref "0") (pin "44") (pinfunction "D1_44") (pintype "bidirectional"))
      (node (ref "1") (pin "44") (pinfunction "D1_44") (pintype "bidirectional"))
      (node (ref "2") (pin "44") (pinfunction "D1_44") (pintype "bidirectional"))
      (node (ref "3") (pin "44") (pinfunction "D1_44") (pintype "bidirectional"))
      (node (ref "4") (pin "44") (pinfunction "D1_44") (pintype "bidirectional"))
      (node (ref "5") (pin "44") (pinfunction "D1_44") (pintype "bidirectional"))
      (node (ref "6") (pin "44") (pinfunction "D1_44") (pintype "bidirectional"))
      (node (ref "7") (pin "44") (pinfunction "D1_44") (pintype "bidirectional"))
      (node (ref "RN2") (pin "9") (pinfunction "9_9") (pintype "passive"))
      (node (ref "RN8") (pin "9") (pinfunction "9_9") (pintype "passive"))
    )
    (net (code "29") (name "D2") (class "Default")
      (node (ref "0") (pin "45") (pinfunction "D2_45") (pintype "bidirectional"))
      (node (ref "1") (pin "45") (pinfunction "D2_45") (pintype "bidirectional"))
      (node (ref "2") (pin "45") (pinfunction "D2_45") (pintype "bidirectional"))
      (node (ref "3") (pin "45") (pinfunction "D2_45") (pintype "bidirectional"))
      (node (ref "4") (pin "45") (pinfunction "D2_45") (pintype "bidirectional"))
      (node (ref "5") (pin "45") (pinfunction "D2_45") (pintype "bidirectional"))
      (node (ref "6") (pin "45") (pinfunction "D2_45") (pintype "bidirectional"))
      (node (ref "7") (pin "45") (pinfunction "D2_45") (pintype "bidirectional"))
      (node (ref "RN12") (pin "9") (pinfunction "9_9") (pintype "passive"))
      (node (ref "RN6") (pin "9") (pinfunction "9_9") (pintype "passive"))
    )
    (net (code "30") (name "D3") (class "Default")
      (node (ref "0") (pin "46") (pinfunction "D3_46") (pintype "bidirectional"))
      (node (ref "1") (pin "46") (pinfunction "D3_46") (pintype "bidirectional"))
      (node (ref "2") (pin "46") (pinfunction "D3_46") (pintype "bidirectional"))
      (node (ref "3") (pin "46") (pinfunction "D3_46") (pintype "bidirectional"))
      (node (ref "4") (pin "46") (pinfunction "D3_46") (pintype "bidirectional"))
      (node (ref "5") (pin "46") (pinfunction "D3_46") (pintype "bidirectional"))
      (node (ref "6") (pin "46") (pinfunction "D3_46") (pintype "bidirectional"))
      (node (ref "7") (pin "46") (pinfunction "D3_46") (pintype "bidirectional"))
      (node (ref "RN3") (pin "9") (pinfunction "9_9") (pintype "passive"))
      (node (ref "RN9") (pin "9") (pinfunction "9_9") (pintype "passive"))
    )
    (net (code "31") (name "D4") (class "Default")
      (node (ref "0") (pin "47") (pinfunction "D4_47") (pintype "bidirectional"))
      (node (ref "1") (pin "47") (pinfunction "D4_47") (pintype "bidirectional"))
      (node (ref "2") (pin "47") (pinfunction "D4_47") (pintype "bidirectional"))
      (node (ref "3") (pin "47") (pinfunction "D4_47") (pintype "bidirectional"))
      (node (ref "4") (pin "47") (pinfunction "D4_47") (pintype "bidirectional"))
      (node (ref "5") (pin "47") (pinfunction "D4_47") (pintype "bidirectional"))
      (node (ref "6") (pin "47") (pinfunction "D4_47") (pintype "bidirectional"))
      (node (ref "7") (pin "47") (pinfunction "D4_47") (pintype "bidirectional"))
      (node (ref "RN12") (pin "8") (pinfunction "8_8") (pintype "passive"))
      (node (ref "RN6") (pin "8") (pinfunction "8_8") (pintype "passive"))
    )
    (net (code "32") (name "D5") (class "Default")
      (node (ref "0") (pin "48") (pinfunction "D5_48") (pintype "bidirectional"))
      (node (ref "1") (pin "48") (pinfunction "D5_48") (pintype "bidirectional"))
      (node (ref "2") (pin "48") (pinfunction "D5_48") (pintype "bidirectional"))
      (node (ref "3") (pin "48") (pinfunction "D5_48") (pintype "bidirectional"))
      (node (ref "4") (pin "48") (pinfunction "D5_48") (pintype "bidirectional"))
      (node (ref "5") (pin "48") (pinfunction "D5_48") (pintype "bidirectional"))
      (node (ref "6") (pin "48") (pinfunction "D5_48") (pintype "bidirectional"))
      (node (ref "7") (pin "48") (pinfunction "D5_48") (pintype "bidirectional"))
      (node (ref "RN3") (pin "8") (pinfunction "8_8") (pintype "passive"))
      (node (ref "RN9") (pin "8") (pinfunction "8_8") (pintype "passive"))
    )
    (net (code "33") (name "D6") (class "Default")
      (node (ref "0") (pin "49") (pinfunction "D6_49") (pintype "bidirectional"))
      (node (ref "1") (pin "49") (pinfunction "D6_49") (pintype "bidirectional"))
      (node (ref "2") (pin "49") (pinfunction "D6_49") (pintype "bidirectional"))
      (node (ref "3") (pin "49") (pinfunction "D6_49") (pintype "bidirectional"))
      (node (ref "4") (pin "49") (pinfunction "D6_49") (pintype "bidirectional"))
      (node (ref "5") (pin "49") (pinfunction "D6_49") (pintype "bidirectional"))
      (node (ref "6") (pin "49") (pinfunction "D6_49") (pintype "bidirectional"))
      (node (ref "7") (pin "49") (pinfunction "D6_49") (pintype "bidirectional"))
      (node (ref "RN12") (pin "7") (pinfunction "7_7") (pintype "passive"))
      (node (ref "RN6") (pin "7") (pinfunction "7_7") (pintype "passive"))
    )
    (net (code "34") (name "D7") (class "Default")
      (node (ref "0") (pin "50") (pinfunction "D7_50") (pintype "bidirectional"))
      (node (ref "1") (pin "50") (pinfunction "D7_50") (pintype "bidirectional"))
      (node (ref "2") (pin "50") (pinfunction "D7_50") (pintype "bidirectional"))
      (node (ref "3") (pin "50") (pinfunction "D7_50") (pintype "bidirectional"))
      (node (ref "4") (pin "50") (pinfunction "D7_50") (pintype "bidirectional"))
      (node (ref "5") (pin "50") (pinfunction "D7_50") (pintype "bidirectional"))
      (node (ref "6") (pin "50") (pinfunction "D7_50") (pintype "bidirectional"))
      (node (ref "7") (pin "50") (pinfunction "D7_50") (pintype "bidirectional"))
      (node (ref "RN3") (pin "7") (pinfunction "7_7") (pintype "passive"))
      (node (ref "RN9") (pin "7") (pinfunction "7_7") (pintype "passive"))
    )
    (net (code "35") (name "GND") (class "Default")
      (node (ref "0") (pin "3") (pinfunction "GND_3") (pintype "bidirectional"))
      (node (ref "0") (pin "4") (pinfunction "GND_4") (pintype "bidirectional"))
      (node (ref "0") (pin "62") (pinfunction "GND_62") (pintype "bidirectional"))
      (node (ref "1") (pin "3") (pinfunction "GND_3") (pintype "bidirectional"))
      (node (ref "1") (pin "4") (pinfunction "GND_4") (pintype "bidirectional"))
      (node (ref "1") (pin "62") (pinfunction "GND_62") (pintype "bidirectional"))
      (node (ref "2") (pin "3") (pinfunction "GND_3") (pintype "bidirectional"))
      (node (ref "2") (pin "4") (pinfunction "GND_4") (pintype "bidirectional"))
      (node (ref "2") (pin "62") (pinfunction "GND_62") (pintype "bidirectional"))
      (node (ref "3") (pin "3") (pinfunction "GND_3") (pintype "bidirectional"))
      (node (ref "3") (pin "4") (pinfunction "GND_4") (pintype "bidirectional"))
      (node (ref "3") (pin "62") (pinfunction "GND_62") (pintype "bidirectional"))
      (node (ref "4") (pin "3") (pinfunction "GND_3") (pintype "bidirectional"))
      (node (ref "4") (pin "4") (pinfunction "GND_4") (pintype "bidirectional"))
      (node (ref "4") (pin "62") (pinfunction "GND_62") (pintype "bidirectional"))
      (node (ref "5") (pin "3") (pinfunction "GND_3") (pintype "bidirectional"))
      (node (ref "5") (pin "4") (pinfunction "GND_4") (pintype "bidirectional"))
      (node (ref "5") (pin "62") (pinfunction "GND_62") (pintype "bidirectional"))
      (node (ref "6") (pin "3") (pinfunction "GND_3") (pintype "bidirectional"))
      (node (ref "6") (pin "4") (pinfunction "GND_4") (pintype "bidirectional"))
      (node (ref "6") (pin "62") (pinfunction "GND_62") (pintype "bidirectional"))
      (node (ref "7") (pin "3") (pinfunction "GND_3") (pintype "bidirectional"))
      (node (ref "7") (pin "4") (pinfunction "GND_4") (pintype "bidirectional"))
      (node (ref "7") (pin "62") (pinfunction "GND_62") (pintype "bidirectional"))
      (node (ref "C1") (pin "2") (pinfunction "2_2") (pintype "passive"))
      (node (ref "C10") (pin "2") (pinfunction "2_2") (pintype "passive"))
      (node (ref "C11") (pin "2") (pinfunction "2_2") (pintype "passive"))
      (node (ref "C12") (pin "2") (pinfunction "2_2") (pintype "passive"))
      (node (ref "C13") (pin "2") (pinfunction "2_2") (pintype "passive"))
      (node (ref "C14") (pin "2") (pinfunction "2_2") (pintype "passive"))
      (node (ref "C15") (pin "2") (pinfunction "2_2") (pintype "passive"))
      (node (ref "C16") (pin "2") (pinfunction "2_2") (pintype "passive"))
      (node (ref "C17") (pin "2") (pinfunction "2_2") (pintype "passive"))
      (node (ref "C18") (pin "2") (pinfunction "2_2") (pintype "passive"))
      (node (ref "C19") (pin "2") (pinfunction "2_2") (pintype "passive"))
      (node (ref "C2") (pin "2") (pinfunction "2_2") (pintype "passive"))
      (node (ref "C20") (pin "2") (pinfunction "2_2") (pintype "passive"))
      (node (ref "C21") (pin "2") (pinfunction "2_2") (pintype "passive"))
      (node (ref "C22") (pin "2") (pinfunction "2_2") (pintype "passive"))
      (node (ref "C23") (pin "2") (pinfunction "2_2") (pintype "passive"))
      (node (ref "C24") (pin "2") (pinfunction "2_2") (pintype "passive"))
      (node (ref "C25") (pin "2") (pinfunction "2_2") (pintype "passive"))
      (node (ref "C26") (pin "2") (pinfunction "2_2") (pintype "passive"))
      (node (ref "C27") (pin "2") (pinfunction "2_2") (pintype "passive"))
      (node (ref "C28") (pin "2") (pinfunction "2_2") (pintype "passive"))
      (node (ref "C29") (pin "2") (pinfunction "2_2") (pintype "passive"))
      (node (ref "C3") (pin "2") (pinfunction "2_2") (pintype "passive"))
      (node (ref "C30") (pin "2") (pinfunction "2_2") (pintype "passive"))
      (node (ref "C31") (pin "2") (pinfunction "2_2") (pintype "passive"))
      (node (ref "C32") (pin "2") (pinfunction "2_2") (pintype "passive"))
      (node (ref "C34") (pin "2") (pinfunction "2_2") (pintype "passive"))
      (node (ref "C35") (pin "2") (pinfunction "2_2") (pintype "passive"))
      (node (ref "C36") (pin "2") (pinfunction "2_2") (pintype "passive"))
      (node (ref "C37") (pin "2") (pinfunction "2_2") (pintype "passive"))
      (node (ref "C38") (pin "2") (pinfunction "2_2") (pintype "passive"))
      (node (ref "C39") (pin "2") (pinfunction "2_2") (pintype "passive"))
      (node (ref "C4") (pin "2") (pinfunction "2_2") (pintype "passive"))
      (node (ref "C40") (pin "2") (pinfunction "2_2") (pintype "passive"))
      (node (ref "C41") (pin "2") (pinfunction "2_2") (pintype "passive"))
      (node (ref "C42") (pin "2") (pinfunction "2_2") (pintype "passive"))
      (node (ref "C43") (pin "2") (pinfunction "2_2") (pintype "passive"))
      (node (ref "C44") (pin "2") (pinfunction "2_2") (pintype "passive"))
      (node (ref "C45") (pin "-") (pinfunction "-_-") (pintype "passive"))
      (node (ref "C46") (pin "2") (pinfunction "2_2") (pintype "passive"))
      (node (ref "C47") (pin "-") (pinfunction "-_-") (pintype "passive"))
      (node (ref "C48") (pin "+") (pinfunction "+_+") (pintype "passive"))
      (node (ref "C49") (pin "-") (pinfunction "-_-") (pintype "passive"))
      (node (ref "C5") (pin "2") (pinfunction "2_2") (pintype "passive"))
      (node (ref "C50") (pin "-") (pinfunction "-_-") (pintype "passive"))
      (node (ref "C51") (pin "-") (pinfunction "-_-") (pintype "passive"))
      (node (ref "C52") (pin "2") (pinfunction "2_2") (pintype "passive"))
      (node (ref "C53") (pin "2") (pinfunction "2_2") (pintype "passive"))
      (node (ref "C54") (pin "2") (pinfunction "2_2") (pintype "passive"))
      (node (ref "C55") (pin "2") (pinfunction "2_2") (pintype "passive"))
      (node (ref "C57") (pin "-") (pinfunction "-_-") (pintype "passive"))
      (node (ref "C6") (pin "2") (pinfunction "2_2") (pintype "passive"))
      (node (ref "C7") (pin "2") (pinfunction "2_2") (pintype "passive"))
      (node (ref "C8") (pin "2") (pinfunction "2_2") (pintype "passive"))
      (node (ref "C9") (pin "2") (pinfunction "2_2") (pintype "passive"))
      (node (ref "D3") (pin "K") (pinfunction "C_K") (pintype "passive"))
      (node (ref "J1") (pin "15") (pinfunction "GND_15") (pintype "bidirectional"))
      (node (ref "J1") (pin "17") (pinfunction "GND_17") (pintype "bidirectional"))
      (node (ref "J1") (pin "18") (pinfunction "GND_18") (pintype "bidirectional"))
      (node (ref "J1") (pin "19") (pinfunction "GND_19") (pintype "bidirectional"))
      (node (ref "J1") (pin "24") (pinfunction "GND_24") (pintype "bidirectional"))
      (node (ref "J1") (pin "3") (pinfunction "GND_3") (pintype "bidirectional"))
      (node (ref "J1") (pin "5") (pinfunction "GND_5") (pintype "bidirectional"))
      (node (ref "J1") (pin "7") (pinfunction "GND_7") (pintype "bidirectional"))
      (node (ref "J2") (pin "2") (pinfunction "2_2") (pintype "passive"))
      (node (ref "JP5") (pin "3") (pinfunction "3_3") (pintype "passive"))
      (node (ref "Q1") (pin "1") (pinfunction "E_1") (pintype "passive"))
      (node (ref "Q3") (pin "1") (pinfunction "E_1") (pintype "passive"))
      (node (ref "R5") (pin "1") (pinfunction "1_1") (pintype "passive"))
      (node (ref "RN15") (pin "1") (pinfunction "1_1") (pintype "passive"))
      (node (ref "S1") (pin "P$1") (pinfunction "P$1_P$1") (pintype "bidirectional"))
      (node (ref "U5") (pin "2") (pinfunction "GND_2") (pintype "passive"))
      (node (ref "U9") (pin "1") (pinfunction "GND_1") (pintype "power_in"))
    )
    (net (code "36") (name "Net-(C34-Pad1)") (class "Default")
      (node (ref "C34") (pin "1") (pinfunction "1_1") (pintype "passive"))
      (node (ref "C35") (pin "1") (pinfunction "1_1") (pintype "passive"))
      (node (ref "C36") (pin "1") (pinfunction "1_1") (pintype "passive"))
      (node (ref "JP1") (pin "2") (pinfunction "2_2") (pintype "passive"))
      (node (ref "R1") (pin "1") (pinfunction "1_1") (pintype "passive"))
      (node (ref "RN1") (pin "1") (pinfunction "1_1") (pintype "passive"))
      (node (ref "RN2") (pin "1") (pinfunction "1_1") (pintype "passive"))
      (node (ref "RN3") (pin "1") (pinfunction "1_1") (pintype "passive"))
      (node (ref "RN4") (pin "1") (pinfunction "1_1") (pintype "passive"))
      (node (ref "RN5") (pin "1") (pinfunction "1_1") (pintype "passive"))
      (node (ref "RN6") (pin "1") (pinfunction "1_1") (pintype "passive"))
    )
    (net (code "37") (name "Net-(C37-Pad1)") (class "Default")
      (node (ref "C37") (pin "1") (pinfunction "1_1") (pintype "passive"))
      (node (ref "C38") (pin "1") (pinfunction "1_1") (pintype "passive"))
      (node (ref "C39") (pin "1") (pinfunction "1_1") (pintype "passive"))
      (node (ref "JP2") (pin "2") (pinfunction "2_2") (pintype "passive"))
      (node (ref "R2") (pin "1") (pinfunction "1_1") (pintype "passive"))
      (node (ref "RN10") (pin "1") (pinfunction "1_1") (pintype "passive"))
      (node (ref "RN11") (pin "1") (pinfunction "1_1") (pintype "passive"))
      (node (ref "RN12") (pin "1") (pinfunction "1_1") (pintype "passive"))
      (node (ref "RN7") (pin "1") (pinfunction "1_1") (pintype "passive"))
      (node (ref "RN8") (pin "1") (pinfunction "1_1") (pintype "passive"))
      (node (ref "RN9") (pin "1") (pinfunction "1_1") (pintype "passive"))
    )
    (net (code "38") (name "Net-(C56-Pad2)") (class "Default")
      (node (ref "C56") (pin "2") (pinfunction "2_2") (pintype "passive"))
      (node (ref "D4") (pin "A") (pinfunction "A_A") (pintype "passive"))
      (node (ref "JP5") (pin "2") (pinfunction "2_2") (pintype "passive"))
    )
    (net (code "39") (name "Net-(D1-PadA)") (class "Default")
      (node (ref "D1") (pin "A") (pinfunction "A_A") (pintype "passive"))
      (node (ref "JP3") (pin "1") (pinfunction "1_1") (pintype "passive"))
    )
    (net (code "40") (name "Net-(D2-C)") (class "Default")
      (node (ref "D2") (pin "K") (pinfunction "C_K") (pintype "passive"))
      (node (ref "JP5") (pin "1") (pinfunction "1_1") (pintype "passive"))
      (node (ref "Q1") (pin "3") (pinfunction "C_3") (pintype "passive"))
      (node (ref "R13") (pin "1") (pinfunction "1_1") (pintype "passive"))
    )
    (net (code "41") (name "Net-(D2-PadA)") (class "Default")
      (node (ref "D2") (pin "A") (pinfunction "A_A") (pintype "passive"))
      (node (ref "R11") (pin "1") (pinfunction "1_1") (pintype "passive"))
    )
    (net (code "42") (name "Net-(D3-PadA)") (class "Default")
      (node (ref "D3") (pin "A") (pinfunction "A_A") (pintype "passive"))
      (node (ref "R12") (pin "1") (pinfunction "1_1") (pintype "passive"))
    )
    (net (code "43") (name "Net-(D4-PadC)") (class "Default")
      (node (ref "D4") (pin "C") (pinfunction "C_C") (pintype "passive"))
      (node (ref "D5") (pin "C") (pinfunction "C_C") (pintype "passive"))
      (node (ref "R9") (pin "1") (pinfunction "1_1") (pintype "passive"))
    )
    (net (code "44") (name "Net-(J1-PS_ON)") (class "Default")
      (node (ref "J1") (pin "16") (pinfunction "PS_ON_16") (pintype "bidirectional"))
      (node (ref "J2") (pin "1") (pinfunction "1_1") (pintype "passive"))
      (node (ref "S1") (pin "P$2") (pinfunction "P$2_P$2") (pintype "bidirectional"))
    )
    (net (code "45") (name "Net-(Q1-B)") (class "Default")
      (node (ref "Q1") (pin "2") (pinfunction "B_2") (pintype "passive"))
      (node (ref "R6") (pin "2") (pinfunction "2_2") (pintype "passive"))
    )
    (net (code "46") (name "Net-(Q2-B)") (class "Default")
      (node (ref "Q2") (pin "2") (pinfunction "B_2") (pintype "passive"))
      (node (ref "R10") (pin "2") (pinfunction "2_2") (pintype "passive"))
    )
    (net (code "47") (name "Net-(Q2-C)") (class "Default")
      (node (ref "Q2") (pin "3") (pinfunction "C_3") (pintype "passive"))
      (node (ref "R12") (pin "2") (pinfunction "2_2") (pintype "passive"))
    )
    (net (code "48") (name "Net-(Q3-B)") (class "Default")
      (node (ref "Q3") (pin "2") (pinfunction "B_2") (pintype "passive"))
      (node (ref "R9") (pin "2") (pinfunction "2_2") (pintype "passive"))
    )
    (net (code "49") (name "Net-(Q3-C)") (class "Default")
      (node (ref "JP7") (pin "1") (pinfunction "1_1") (pintype "passive"))
      (node (ref "Q3") (pin "3") (pinfunction "C_3") (pintype "passive"))
    )
    (net (code "50") (name "Net-(U1A-I0)") (class "Default")
      (node (ref "U1") (pin "1") (pinfunction "I0_1") (pintype "input"))
      (node (ref "U2") (pin "2") (pinfunction "O_2") (pintype "output"))
    )
    (net (code "51") (name "Net-(U1A-O)") (class "Default")
      (node (ref "R3") (pin "1") (pinfunction "1_1") (pintype "passive"))
      (node (ref "U1") (pin "3") (pinfunction "O_3") (pintype "output"))
    )
    (net (code "52") (name "Net-(U2A-I)") (class "Default")
      (node (ref "U2") (pin "1") (pinfunction "I_1") (pintype "input"))
      (node (ref "U3") (pin "8") (pinfunction "O_8") (pintype "output"))
    )
    (net (code "53") (name "Net-(U2B-I)") (class "Default")
      (node (ref "U2") (pin "3") (pinfunction "I_3") (pintype "input"))
      (node (ref "U4") (pin "8") (pinfunction "O_8") (pintype "output"))
    )
    (net (code "54") (name "Net-(U2B-O)") (class "Default")
      (node (ref "R4") (pin "1") (pinfunction "1_1") (pintype "passive"))
      (node (ref "U2") (pin "4") (pinfunction "O_4") (pintype "output"))
    )
    (net (code "55") (name "Net-(U5-VI)") (class "Default")
      (node (ref "C44") (pin "1") (pinfunction "1_1") (pintype "passive"))
      (node (ref "D1") (pin "C") (pinfunction "C_C") (pintype "passive"))
      (node (ref "U5") (pin "1") (pinfunction "VI_1") (pintype "input"))
    )
    (net (code "56") (name "Net-(U5-VO)") (class "Default")
      (node (ref "C45") (pin "+") (pinfunction "+_+") (pintype "passive"))
      (node (ref "C46") (pin "1") (pinfunction "1_1") (pintype "passive"))
      (node (ref "JP1") (pin "3") (pinfunction "3_3") (pintype "passive"))
      (node (ref "JP2") (pin "3") (pinfunction "3_3") (pintype "passive"))
      (node (ref "U5") (pin "3") (pinfunction "VO_3") (pintype "passive"))
    )
    (net (code "57") (name "Net-(U8A-G)") (class "Default")
      (node (ref "JP4") (pin "2") (pinfunction "2_2") (pintype "passive"))
      (node (ref "R5") (pin "2") (pinfunction "2_2") (pintype "passive"))
      (node (ref "U8") (pin "1") (pinfunction "G_1") (pintype "input"))
    )
    (net (code "58") (name "Net-(U8A-Q0)") (class "Default")
      (node (ref "RN15") (pin "9") (pinfunction "9_9") (pintype "passive"))
      (node (ref "S2") (pin "9") (pinfunction "9_9") (pintype "passive"))
      (node (ref "U8") (pin "3") (pinfunction "Q0_3") (pintype "input"))
    )
    (net (code "59") (name "Net-(U8A-Q1)") (class "Default")
      (node (ref "RN15") (pin "7") (pinfunction "7_7") (pintype "passive"))
      (node (ref "S2") (pin "11") (pinfunction "11_11") (pintype "passive"))
      (node (ref "U8") (pin "5") (pinfunction "Q1_5") (pintype "input"))
    )
    (net (code "60") (name "Net-(U8A-Q2)") (class "Default")
      (node (ref "RN15") (pin "5") (pinfunction "5_5") (pintype "passive"))
      (node (ref "S2") (pin "13") (pinfunction "13_13") (pintype "passive"))
      (node (ref "U8") (pin "7") (pinfunction "Q2_7") (pintype "input"))
    )
    (net (code "61") (name "Net-(U8A-Q3)") (class "Default")
      (node (ref "RN15") (pin "3") (pinfunction "3_3") (pintype "passive"))
      (node (ref "S2") (pin "15") (pinfunction "15_15") (pintype "passive"))
      (node (ref "U8") (pin "9") (pinfunction "Q3_9") (pintype "input"))
    )
    (net (code "62") (name "Net-(U8A-Q4)") (class "Default")
      (node (ref "RN15") (pin "2") (pinfunction "2_2") (pintype "passive"))
      (node (ref "S2") (pin "16") (pinfunction "16_16") (pintype "passive"))
      (node (ref "U8") (pin "12") (pinfunction "Q4_12") (pintype "input"))
    )
    (net (code "63") (name "Net-(U8A-Q5)") (class "Default")
      (node (ref "RN15") (pin "4") (pinfunction "4_4") (pintype "passive"))
      (node (ref "S2") (pin "14") (pinfunction "14_14") (pintype "passive"))
      (node (ref "U8") (pin "14") (pinfunction "Q5_14") (pintype "input"))
    )
    (net (code "64") (name "Net-(U8A-Q6)") (class "Default")
      (node (ref "RN15") (pin "6") (pinfunction "6_6") (pintype "passive"))
      (node (ref "S2") (pin "12") (pinfunction "12_12") (pintype "passive"))
      (node (ref "U8") (pin "16") (pinfunction "Q6_16") (pintype "input"))
    )
    (net (code "65") (name "Net-(U8A-Q7)") (class "Default")
      (node (ref "RN15") (pin "8") (pinfunction "8_8") (pintype "passive"))
      (node (ref "S2") (pin "10") (pinfunction "10_10") (pintype "passive"))
      (node (ref "U8") (pin "18") (pinfunction "Q7_18") (pintype "input"))
    )
    (net (code "66") (name "Net-(U9-CON)") (class "Default")
      (node (ref "C55") (pin "1") (pinfunction "1_1") (pintype "passive"))
      (node (ref "U9") (pin "5") (pinfunction "CON_5") (pintype "input"))
    )
    (net (code "67") (name "Net-(U9-DIS)") (class "Default")
      (node (ref "C57") (pin "+") (pinfunction "+_+") (pintype "passive"))
      (node (ref "R8") (pin "2") (pinfunction "2_2") (pintype "passive"))
      (node (ref "U9") (pin "6") (pinfunction "TRE_6") (pintype "input"))
      (node (ref "U9") (pin "7") (pinfunction "DIS_7") (pintype "input"))
    )
    (net (code "68") (name "Net-(U9-OUT)") (class "Default")
      (node (ref "D5") (pin "A") (pinfunction "A_A") (pintype "passive"))
      (node (ref "U9") (pin "3") (pinfunction "OUT_3") (pintype "output"))
    )
    (net (code "69") (name "Net-(U9-TRI)") (class "Default")
      (node (ref "C56") (pin "1") (pinfunction "1_1") (pintype "passive"))
      (node (ref "R7") (pin "2") (pinfunction "2_2") (pintype "passive"))
      (node (ref "U9") (pin "2") (pinfunction "TRI_2") (pintype "input"))
    )
    (net (code "70") (name "Net-(U9-VCC+)") (class "Default")
      (node (ref "C54") (pin "1") (pinfunction "1_1") (pintype "passive"))
      (node (ref "JP6") (pin "2") (pinfunction "2_2") (pintype "passive"))
      (node (ref "R11") (pin "2") (pinfunction "2_2") (pintype "passive"))
      (node (ref "R13") (pin "2") (pinfunction "2_2") (pintype "passive"))
      (node (ref "R7") (pin "1") (pinfunction "1_1") (pintype "passive"))
      (node (ref "R8") (pin "1") (pinfunction "1_1") (pintype "passive"))
      (node (ref "U9") (pin "4") (pinfunction "/RES_4") (pintype "input"))
      (node (ref "U9") (pin "8") (pinfunction "VCC+_8") (pintype "power_in"))
    )
    (net (code "71") (name "PG") (class "Default")
      (node (ref "J1") (pin "8") (pinfunction "PWR_OK_8") (pintype "bidirectional"))
      (node (ref "R6") (pin "1") (pinfunction "1_1") (pintype "passive"))
    )
    (net (code "72") (name "VCC") (class "Default")
      (node (ref "0") (pin "5") (pinfunction "+5V_5") (pintype "bidirectional"))
      (node (ref "0") (pin "6") (pinfunction "+5V_6") (pintype "bidirectional"))
      (node (ref "1") (pin "5") (pinfunction "+5V_5") (pintype "bidirectional"))
      (node (ref "1") (pin "6") (pinfunction "+5V_6") (pintype "bidirectional"))
      (node (ref "2") (pin "5") (pinfunction "+5V_5") (pintype "bidirectional"))
      (node (ref "2") (pin "6") (pinfunction "+5V_6") (pintype "bidirectional"))
      (node (ref "3") (pin "5") (pinfunction "+5V_5") (pintype "bidirectional"))
      (node (ref "3") (pin "6") (pinfunction "+5V_6") (pintype "bidirectional"))
      (node (ref "4") (pin "5") (pinfunction "+5V_5") (pintype "bidirectional"))
      (node (ref "4") (pin "6") (pinfunction "+5V_6") (pintype "bidirectional"))
      (node (ref "5") (pin "5") (pinfunction "+5V_5") (pintype "bidirectional"))
      (node (ref "5") (pin "6") (pinfunction "+5V_6") (pintype "bidirectional"))
      (node (ref "6") (pin "5") (pinfunction "+5V_5") (pintype "bidirectional"))
      (node (ref "6") (pin "6") (pinfunction "+5V_6") (pintype "bidirectional"))
      (node (ref "7") (pin "5") (pinfunction "+5V_5") (pintype "bidirectional"))
      (node (ref "7") (pin "6") (pinfunction "+5V_6") (pintype "bidirectional"))
      (node (ref "C10") (pin "1") (pinfunction "1_1") (pintype "passive"))
      (node (ref "C14") (pin "1") (pinfunction "1_1") (pintype "passive"))
      (node (ref "C18") (pin "1") (pinfunction "1_1") (pintype "passive"))
      (node (ref "C2") (pin "1") (pinfunction "1_1") (pintype "passive"))
      (node (ref "C22") (pin "1") (pinfunction "1_1") (pintype "passive"))
      (node (ref "C26") (pin "1") (pinfunction "1_1") (pintype "passive"))
      (node (ref "C30") (pin "1") (pinfunction "1_1") (pintype "passive"))
      (node (ref "C40") (pin "1") (pinfunction "1_1") (pintype "passive"))
      (node (ref "C41") (pin "1") (pinfunction "1_1") (pintype "passive"))
      (node (ref "C42") (pin "1") (pinfunction "1_1") (pintype "passive"))
      (node (ref "C43") (pin "1") (pinfunction "1_1") (pintype "passive"))
      (node (ref "C49") (pin "+") (pinfunction "+_+") (pintype "passive"))
      (node (ref "C52") (pin "1") (pinfunction "1_1") (pintype "passive"))
      (node (ref "C53") (pin "1") (pinfunction "1_1") (pintype "passive"))
      (node (ref "C6") (pin "1") (pinfunction "1_1") (pintype "passive"))
      (node (ref "J1") (pin "21") (pinfunction "5V_21") (pintype "bidirectional"))
      (node (ref "J1") (pin "22") (pinfunction "5V_22") (pintype "bidirectional"))
      (node (ref "J1") (pin "23") (pinfunction "5V_23") (pintype "bidirectional"))
      (node (ref "J1") (pin "4") (pinfunction "5V_4") (pintype "bidirectional"))
      (node (ref "J1") (pin "6") (pinfunction "5V_6") (pintype "bidirectional"))
      (node (ref "JP1") (pin "1") (pinfunction "1_1") (pintype "passive"))
      (node (ref "JP2") (pin "1") (pinfunction "1_1") (pintype "passive"))
      (node (ref "JP3") (pin "2") (pinfunction "2_2") (pintype "passive"))
      (node (ref "JP4") (pin "1") (pinfunction "1_1") (pintype "passive"))
      (node (ref "JP6") (pin "1") (pinfunction "1_1") (pintype "passive"))
      (node (ref "RN13") (pin "1") (pinfunction "1_1") (pintype "passive"))
      (node (ref "RN14") (pin "1") (pinfunction "1_1") (pintype "passive"))
      (node (ref "S2") (pin "1") (pinfunction "1_1") (pintype "passive"))
      (node (ref "S2") (pin "2") (pinfunction "2_2") (pintype "passive"))
      (node (ref "S2") (pin "3") (pinfunction "3_3") (pintype "passive"))
      (node (ref "S2") (pin "4") (pinfunction "4_4") (pintype "passive"))
      (node (ref "S2") (pin "5") (pinfunction "5_5") (pintype "passive"))
      (node (ref "S2") (pin "6") (pinfunction "6_6") (pintype "passive"))
      (node (ref "S2") (pin "7") (pinfunction "7_7") (pintype "passive"))
      (node (ref "S2") (pin "8") (pinfunction "8_8") (pintype "passive"))
      (node (ref "U1") (pin "10") (pinfunction "I1_10") (pintype "input"))
      (node (ref "U1") (pin "12") (pinfunction "I0_12") (pintype "input"))
      (node (ref "U1") (pin "13") (pinfunction "I1_13") (pintype "input"))
      (node (ref "U1") (pin "4") (pinfunction "I0_4") (pintype "input"))
      (node (ref "U1") (pin "5") (pinfunction "I1_5") (pintype "input"))
      (node (ref "U1") (pin "9") (pinfunction "I0_9") (pintype "input"))
      (node (ref "U2") (pin "11") (pinfunction "I_11") (pintype "input"))
      (node (ref "U2") (pin "13") (pinfunction "I_13") (pintype "input"))
      (node (ref "U2") (pin "5") (pinfunction "I_5") (pintype "input"))
      (node (ref "U2") (pin "9") (pinfunction "I_9") (pintype "input"))
      (node (ref "U7") (pin "6") (pinfunction "G1_6") (pintype "input"))
    )
    (net (code "73") (name "unconnected-(J1-3.3V-Pad12)") (class "Default")
      (node (ref "J1") (pin "12") (pinfunction "3.3V_12") (pintype "bidirectional"))
    )
    (net (code "74") (name "unconnected-(J1-NC-Pad20)") (class "Default")
      (node (ref "J1") (pin "20") (pinfunction "NC_20") (pintype "bidirectional"))
    )
    (net (code "75") (name "unconnected-(S1-PadP$3)") (class "Default")
      (node (ref "S1") (pin "P$3") (pinfunction "P$3_P$3") (pintype "bidirectional"))
    )
    (net (code "76") (name "unconnected-(U1B-O-Pad6)") (class "Default")
      (node (ref "U1") (pin "6") (pinfunction "O_6") (pintype "output"))
    )
    (net (code "77") (name "unconnected-(U1C-O-Pad8)") (class "Default")
      (node (ref "U1") (pin "8") (pinfunction "O_8") (pintype "output"))
    )
    (net (code "78") (name "unconnected-(U1D-O-Pad11)") (class "Default")
      (node (ref "U1") (pin "11") (pinfunction "O_11") (pintype "output"))
    )
    (net (code "79") (name "unconnected-(U2C-O-Pad6)") (class "Default")
      (node (ref "U2") (pin "6") (pinfunction "O_6") (pintype "output"))
    )
    (net (code "80") (name "unconnected-(U2D-O-Pad8)") (class "Default")
      (node (ref "U2") (pin "8") (pinfunction "O_8") (pintype "output"))
    )
    (net (code "81") (name "unconnected-(U2E-O-Pad10)") (class "Default")
      (node (ref "U2") (pin "10") (pinfunction "O_10") (pintype "output"))
    )
    (net (code "82") (name "unconnected-(U2F-O-Pad12)") (class "Default")
      (node (ref "U2") (pin "12") (pinfunction "O_12") (pintype "output"))
    )
    (net (code "83") (name "~{BUSACK}") (class "Default")
      (node (ref "0") (pin "20") (pinfunction "~{BUSACK}_20") (pintype "bidirectional"))
      (node (ref "1") (pin "20") (pinfunction "~{BUSACK}_20") (pintype "bidirectional"))
      (node (ref "2") (pin "20") (pinfunction "~{BUSACK}_20") (pintype "bidirectional"))
      (node (ref "3") (pin "20") (pinfunction "~{BUSACK}_20") (pintype "bidirectional"))
      (node (ref "4") (pin "20") (pinfunction "~{BUSACK}_20") (pintype "bidirectional"))
      (node (ref "5") (pin "20") (pinfunction "~{BUSACK}_20") (pintype "bidirectional"))
      (node (ref "6") (pin "20") (pinfunction "~{BUSACK}_20") (pintype "bidirectional"))
      (node (ref "7") (pin "20") (pinfunction "~{BUSACK}_20") (pintype "bidirectional"))
      (node (ref "RN1") (pin "5") (pinfunction "5_5") (pintype "passive"))
      (node (ref "RN7") (pin "5") (pinfunction "5_5") (pintype "passive"))
    )
    (net (code "84") (name "~{BUSRQ0}") (class "Default")
      (node (ref "0") (pin "10") (pinfunction "~{BUSRQ}_10") (pintype "bidirectional"))
      (node (ref "RN14") (pin "2") (pinfunction "2_2") (pintype "passive"))
      (node (ref "U4") (pin "1") (pinfunction "I0_1") (pintype "input"))
    )
    (net (code "85") (name "~{BUSRQ1}") (class "Default")
      (node (ref "1") (pin "10") (pinfunction "~{BUSRQ}_10") (pintype "bidirectional"))
      (node (ref "RN14") (pin "3") (pinfunction "3_3") (pintype "passive"))
      (node (ref "U4") (pin "2") (pinfunction "I1_2") (pintype "input"))
    )
    (net (code "86") (name "~{BUSRQ2}") (class "Default")
      (node (ref "2") (pin "10") (pinfunction "~{BUSRQ}_10") (pintype "bidirectional"))
      (node (ref "RN14") (pin "4") (pinfunction "4_4") (pintype "passive"))
      (node (ref "U4") (pin "3") (pinfunction "I2_3") (pintype "input"))
    )
    (net (code "87") (name "~{BUSRQ3}") (class "Default")
      (node (ref "3") (pin "10") (pinfunction "~{BUSRQ}_10") (pintype "bidirectional"))
      (node (ref "RN14") (pin "5") (pinfunction "5_5") (pintype "passive"))
      (node (ref "U4") (pin "4") (pinfunction "I3_4") (pintype "input"))
    )
    (net (code "88") (name "~{BUSRQ4}") (class "Default")
      (node (ref "4") (pin "10") (pinfunction "~{BUSRQ}_10") (pintype "bidirectional"))
      (node (ref "RN14") (pin "6") (pinfunction "6_6") (pintype "passive"))
      (node (ref "U4") (pin "5") (pinfunction "I4_5") (pintype "input"))
    )
    (net (code "89") (name "~{BUSRQ5}") (class "Default")
      (node (ref "5") (pin "10") (pinfunction "~{BUSRQ}_10") (pintype "bidirectional"))
      (node (ref "RN14") (pin "7") (pinfunction "7_7") (pintype "passive"))
      (node (ref "U4") (pin "6") (pinfunction "I5_6") (pintype "input"))
    )
    (net (code "90") (name "~{BUSRQ6}") (class "Default")
      (node (ref "6") (pin "10") (pinfunction "~{BUSRQ}_10") (pintype "bidirectional"))
      (node (ref "RN14") (pin "8") (pinfunction "8_8") (pintype "passive"))
      (node (ref "U4") (pin "11") (pinfunction "I6_11") (pintype "input"))
    )
    (net (code "91") (name "~{BUSRQ7}") (class "Default")
      (node (ref "7") (pin "10") (pinfunction "~{BUSRQ}_10") (pintype "bidirectional"))
      (node (ref "RN14") (pin "9") (pinfunction "9_9") (pintype "passive"))
      (node (ref "U4") (pin "12") (pinfunction "I7_12") (pintype "input"))
    )
    (net (code "92") (name "~{CBR}") (class "Default")
      (node (ref "0") (pin "12") (pinfunction "~{CBR}_12") (pintype "bidirectional"))
      (node (ref "1") (pin "12") (pinfunction "~{CBR}_12") (pintype "bidirectional"))
      (node (ref "2") (pin "12") (pinfunction "~{CBR}_12") (pintype "bidirectional"))
      (node (ref "3") (pin "12") (pinfunction "~{CBR}_12") (pintype "bidirectional"))
      (node (ref "4") (pin "12") (pinfunction "~{CBR}_12") (pintype "bidirectional"))
      (node (ref "5") (pin "12") (pinfunction "~{CBR}_12") (pintype "bidirectional"))
      (node (ref "6") (pin "12") (pinfunction "~{CBR}_12") (pintype "bidirectional"))
      (node (ref "7") (pin "12") (pinfunction "~{CBR}_12") (pintype "bidirectional"))
      (node (ref "R1") (pin "2") (pinfunction "2_2") (pintype "passive"))
      (node (ref "R2") (pin "2") (pinfunction "2_2") (pintype "passive"))
      (node (ref "R4") (pin "2") (pinfunction "2_2") (pintype "passive"))
    )
    (net (code "93") (name "~{CINH}") (class "Default")
      (node (ref "0") (pin "13") (pinfunction "~{CINH}_13") (pintype "bidirectional"))
      (node (ref "1") (pin "13") (pinfunction "~{CINH}_13") (pintype "bidirectional"))
      (node (ref "2") (pin "13") (pinfunction "~{CINH}_13") (pintype "bidirectional"))
      (node (ref "3") (pin "13") (pinfunction "~{CINH}_13") (pintype "bidirectional"))
      (node (ref "4") (pin "13") (pinfunction "~{CINH}_13") (pintype "bidirectional"))
      (node (ref "5") (pin "13") (pinfunction "~{CINH}_13") (pintype "bidirectional"))
      (node (ref "6") (pin "13") (pinfunction "~{CINH}_13") (pintype "bidirectional"))
      (node (ref "7") (pin "13") (pinfunction "~{CINH}_13") (pintype "bidirectional"))
      (node (ref "R3") (pin "2") (pinfunction "2_2") (pintype "passive"))
      (node (ref "RN10") (pin "2") (pinfunction "2_2") (pintype "passive"))
      (node (ref "RN4") (pin "2") (pinfunction "2_2") (pintype "passive"))
    )
    (net (code "94") (name "~{CS0}") (class "Default")
      (node (ref "0") (pin "9") (pinfunction "~{CSX}_9") (pintype "bidirectional"))
      (node (ref "U7") (pin "15") (pinfunction "Y0_15") (pintype "output"))
    )
    (net (code "95") (name "~{CS1}") (class "Default")
      (node (ref "1") (pin "9") (pinfunction "~{CSX}_9") (pintype "bidirectional"))
      (node (ref "U7") (pin "14") (pinfunction "Y1_14") (pintype "output"))
    )
    (net (code "96") (name "~{CS2}") (class "Default")
      (node (ref "2") (pin "9") (pinfunction "~{CSX}_9") (pintype "bidirectional"))
      (node (ref "U7") (pin "13") (pinfunction "Y2_13") (pintype "output"))
    )
    (net (code "97") (name "~{CS3}") (class "Default")
      (node (ref "3") (pin "9") (pinfunction "~{CSX}_9") (pintype "bidirectional"))
      (node (ref "U7") (pin "12") (pinfunction "Y3_12") (pintype "output"))
    )
    (net (code "98") (name "~{CS4}") (class "Default")
      (node (ref "4") (pin "9") (pinfunction "~{CSX}_9") (pintype "bidirectional"))
      (node (ref "U7") (pin "11") (pinfunction "Y4_11") (pintype "output"))
    )
    (net (code "99") (name "~{CS5}") (class "Default")
      (node (ref "5") (pin "9") (pinfunction "~{CSX}_9") (pintype "bidirectional"))
      (node (ref "U7") (pin "10") (pinfunction "Y5_10") (pintype "output"))
    )
    (net (code "100") (name "~{CS6}") (class "Default")
      (node (ref "6") (pin "9") (pinfunction "~{CSX}_9") (pintype "bidirectional"))
      (node (ref "U7") (pin "9") (pinfunction "Y6_9") (pintype "output"))
    )
    (net (code "101") (name "~{CS7}") (class "Default")
      (node (ref "7") (pin "9") (pinfunction "~{CSX}_9") (pintype "bidirectional"))
      (node (ref "U7") (pin "7") (pinfunction "Y7_7") (pintype "output"))
    )
    (net (code "102") (name "~{FETCH}") (class "Default")
      (node (ref "0") (pin "19") (pinfunction "~{FETCH}_19") (pintype "bidirectional"))
      (node (ref "1") (pin "19") (pinfunction "~{FETCH}_19") (pintype "bidirectional"))
      (node (ref "2") (pin "19") (pinfunction "~{FETCH}_19") (pintype "bidirectional"))
      (node (ref "3") (pin "19") (pinfunction "~{FETCH}_19") (pintype "bidirectional"))
      (node (ref "4") (pin "19") (pinfunction "~{FETCH}_19") (pintype "bidirectional"))
      (node (ref "5") (pin "19") (pinfunction "~{FETCH}_19") (pintype "bidirectional"))
      (node (ref "6") (pin "19") (pinfunction "~{FETCH}_19") (pintype "bidirectional"))
      (node (ref "7") (pin "19") (pinfunction "~{FETCH}_19") (pintype "bidirectional"))
      (node (ref "RN10") (pin "5") (pinfunction "5_5") (pintype "passive"))
      (node (ref "RN4") (pin "5") (pinfunction "5_5") (pintype "passive"))
    )
    (net (code "103") (name "~{HALT}") (class "Default")
      (node (ref "0") (pin "17") (pinfunction "~{HALT}_17") (pintype "bidirectional"))
      (node (ref "1") (pin "17") (pinfunction "~{HALT}_17") (pintype "bidirectional"))
      (node (ref "2") (pin "17") (pinfunction "~{HALT}_17") (pintype "bidirectional"))
      (node (ref "3") (pin "17") (pinfunction "~{HALT}_17") (pintype "bidirectional"))
      (node (ref "4") (pin "17") (pinfunction "~{HALT}_17") (pintype "bidirectional"))
      (node (ref "5") (pin "17") (pinfunction "~{HALT}_17") (pintype "bidirectional"))
      (node (ref "6") (pin "17") (pinfunction "~{HALT}_17") (pintype "bidirectional"))
      (node (ref "7") (pin "17") (pinfunction "~{HALT}_17") (pintype "bidirectional"))
      (node (ref "RN10") (pin "4") (pinfunction "4_4") (pintype "passive"))
      (node (ref "RN4") (pin "4") (pinfunction "4_4") (pintype "passive"))
    )
    (net (code "104") (name "~{INH0}") (class "Default")
      (node (ref "0") (pin "11") (pinfunction "~{INH}_11") (pintype "bidirectional"))
      (node (ref "RN13") (pin "2") (pinfunction "2_2") (pintype "passive"))
      (node (ref "U3") (pin "1") (pinfunction "I0_1") (pintype "input"))
    )
    (net (code "105") (name "~{INH1}") (class "Default")
      (node (ref "1") (pin "11") (pinfunction "~{INH}_11") (pintype "bidirectional"))
      (node (ref "RN13") (pin "3") (pinfunction "3_3") (pintype "passive"))
      (node (ref "U3") (pin "2") (pinfunction "I1_2") (pintype "input"))
    )
    (net (code "106") (name "~{INH2}") (class "Default")
      (node (ref "2") (pin "11") (pinfunction "~{INH}_11") (pintype "bidirectional"))
      (node (ref "RN13") (pin "4") (pinfunction "4_4") (pintype "passive"))
      (node (ref "U3") (pin "3") (pinfunction "I2_3") (pintype "input"))
    )
    (net (code "107") (name "~{INH3}") (class "Default")
      (node (ref "3") (pin "11") (pinfunction "~{INH}_11") (pintype "bidirectional"))
      (node (ref "RN13") (pin "5") (pinfunction "5_5") (pintype "passive"))
      (node (ref "U3") (pin "4") (pinfunction "I3_4") (pintype "input"))
    )
    (net (code "108") (name "~{INH4}") (class "Default")
      (node (ref "4") (pin "11") (pinfunction "~{INH}_11") (pintype "bidirectional"))
      (node (ref "RN13") (pin "6") (pinfunction "6_6") (pintype "passive"))
      (node (ref "U3") (pin "5") (pinfunction "I4_5") (pintype "input"))
    )
    (net (code "109") (name "~{INH5}") (class "Default")
      (node (ref "5") (pin "11") (pinfunction "~{INH}_11") (pintype "bidirectional"))
      (node (ref "RN13") (pin "7") (pinfunction "7_7") (pintype "passive"))
      (node (ref "U3") (pin "6") (pinfunction "I5_6") (pintype "input"))
    )
    (net (code "110") (name "~{INH6}") (class "Default")
      (node (ref "6") (pin "11") (pinfunction "~{INH}_11") (pintype "bidirectional"))
      (node (ref "RN13") (pin "8") (pinfunction "8_8") (pintype "passive"))
      (node (ref "U3") (pin "11") (pinfunction "I6_11") (pintype "input"))
    )
    (net (code "111") (name "~{INH7}") (class "Default")
      (node (ref "7") (pin "11") (pinfunction "~{INH}_11") (pintype "bidirectional"))
      (node (ref "RN13") (pin "9") (pinfunction "9_9") (pintype "passive"))
      (node (ref "U3") (pin "12") (pinfunction "I7_12") (pintype "input"))
    )
    (net (code "112") (name "~{INHPCS}") (class "Default")
      (node (ref "U1") (pin "2") (pinfunction "I1_2") (pintype "input"))
      (node (ref "U7") (pin "5") (pinfunction "G2B_5") (pintype "input"))
      (node (ref "U8") (pin "19") (pinfunction "P=Q_19") (pintype "output"))
    )
    (net (code "113") (name "~{INT}") (class "Default")
      (node (ref "0") (pin "51") (pinfunction "~{INT}_51") (pintype "bidirectional"))
      (node (ref "1") (pin "51") (pinfunction "~{INT}_51") (pintype "bidirectional"))
      (node (ref "2") (pin "51") (pinfunction "~{INT}_51") (pintype "bidirectional"))
      (node (ref "3") (pin "51") (pinfunction "~{INT}_51") (pintype "bidirectional"))
      (node (ref "4") (pin "51") (pinfunction "~{INT}_51") (pintype "bidirectional"))
      (node (ref "5") (pin "51") (pinfunction "~{INT}_51") (pintype "bidirectional"))
      (node (ref "6") (pin "51") (pinfunction "~{INT}_51") (pintype "bidirectional"))
      (node (ref "7") (pin "51") (pinfunction "~{INT}_51") (pintype "bidirectional"))
      (node (ref "RN12") (pin "6") (pinfunction "6_6") (pintype "passive"))
      (node (ref "RN6") (pin "6") (pinfunction "6_6") (pintype "passive"))
    )
    (net (code "114") (name "~{IRQ0}") (class "Default")
      (node (ref "0") (pin "52") (pinfunction "~{IRQX}_52") (pintype "bidirectional"))
      (node (ref "0") (pin "53") (pinfunction "~{IRQ0}_53") (pintype "bidirectional"))
      (node (ref "1") (pin "53") (pinfunction "~{IRQ0}_53") (pintype "bidirectional"))
      (node (ref "2") (pin "53") (pinfunction "~{IRQ0}_53") (pintype "bidirectional"))
      (node (ref "3") (pin "53") (pinfunction "~{IRQ0}_53") (pintype "bidirectional"))
      (node (ref "4") (pin "53") (pinfunction "~{IRQ0}_53") (pintype "bidirectional"))
      (node (ref "5") (pin "53") (pinfunction "~{IRQ0}_53") (pintype "bidirectional"))
      (node (ref "6") (pin "53") (pinfunction "~{IRQ0}_53") (pintype "bidirectional"))
      (node (ref "7") (pin "53") (pinfunction "~{IRQ0}_53") (pintype "bidirectional"))
      (node (ref "RN3") (pin "6") (pinfunction "6_6") (pintype "passive"))
      (node (ref "RN9") (pin "6") (pinfunction "6_6") (pintype "passive"))
    )
    (net (code "115") (name "~{IRQ1}") (class "Default")
      (node (ref "0") (pin "54") (pinfunction "~{IRQ1}_54") (pintype "bidirectional"))
      (node (ref "1") (pin "52") (pinfunction "~{IRQX}_52") (pintype "bidirectional"))
      (node (ref "1") (pin "54") (pinfunction "~{IRQ1}_54") (pintype "bidirectional"))
      (node (ref "2") (pin "54") (pinfunction "~{IRQ1}_54") (pintype "bidirectional"))
      (node (ref "3") (pin "54") (pinfunction "~{IRQ1}_54") (pintype "bidirectional"))
      (node (ref "4") (pin "54") (pinfunction "~{IRQ1}_54") (pintype "bidirectional"))
      (node (ref "5") (pin "54") (pinfunction "~{IRQ1}_54") (pintype "bidirectional"))
      (node (ref "6") (pin "54") (pinfunction "~{IRQ1}_54") (pintype "bidirectional"))
      (node (ref "7") (pin "54") (pinfunction "~{IRQ1}_54") (pintype "bidirectional"))
      (node (ref "RN12") (pin "5") (pinfunction "5_5") (pintype "passive"))
      (node (ref "RN6") (pin "5") (pinfunction "5_5") (pintype "passive"))
    )
    (net (code "116") (name "~{IRQ2}") (class "Default")
      (node (ref "0") (pin "55") (pinfunction "~{IRQ2}_55") (pintype "bidirectional"))
      (node (ref "1") (pin "55") (pinfunction "~{IRQ2}_55") (pintype "bidirectional"))
      (node (ref "2") (pin "52") (pinfunction "~{IRQX}_52") (pintype "bidirectional"))
      (node (ref "2") (pin "55") (pinfunction "~{IRQ2}_55") (pintype "bidirectional"))
      (node (ref "3") (pin "55") (pinfunction "~{IRQ2}_55") (pintype "bidirectional"))
      (node (ref "4") (pin "55") (pinfunction "~{IRQ2}_55") (pintype "bidirectional"))
      (node (ref "5") (pin "55") (pinfunction "~{IRQ2}_55") (pintype "bidirectional"))
      (node (ref "6") (pin "55") (pinfunction "~{IRQ2}_55") (pintype "bidirectional"))
      (node (ref "7") (pin "55") (pinfunction "~{IRQ2}_55") (pintype "bidirectional"))
      (node (ref "RN3") (pin "5") (pinfunction "5_5") (pintype "passive"))
      (node (ref "RN9") (pin "5") (pinfunction "5_5") (pintype "passive"))
    )
    (net (code "117") (name "~{IRQ3}") (class "Default")
      (node (ref "0") (pin "56") (pinfunction "~{IRQ3}_56") (pintype "bidirectional"))
      (node (ref "1") (pin "56") (pinfunction "~{IRQ3}_56") (pintype "bidirectional"))
      (node (ref "2") (pin "56") (pinfunction "~{IRQ3}_56") (pintype "bidirectional"))
      (node (ref "3") (pin "52") (pinfunction "~{IRQX}_52") (pintype "bidirectional"))
      (node (ref "3") (pin "56") (pinfunction "~{IRQ3}_56") (pintype "bidirectional"))
      (node (ref "4") (pin "56") (pinfunction "~{IRQ3}_56") (pintype "bidirectional"))
      (node (ref "5") (pin "56") (pinfunction "~{IRQ3}_56") (pintype "bidirectional"))
      (node (ref "6") (pin "56") (pinfunction "~{IRQ3}_56") (pintype "bidirectional"))
      (node (ref "7") (pin "56") (pinfunction "~{IRQ3}_56") (pintype "bidirectional"))
      (node (ref "RN12") (pin "4") (pinfunction "4_4") (pintype "passive"))
      (node (ref "RN6") (pin "4") (pinfunction "4_4") (pintype "passive"))
    )
    (net (code "118") (name "~{IRQ4}") (class "Default")
      (node (ref "0") (pin "57") (pinfunction "~{IRQ4}_57") (pintype "bidirectional"))
      (node (ref "1") (pin "57") (pinfunction "~{IRQ4}_57") (pintype "bidirectional"))
      (node (ref "2") (pin "57") (pinfunction "~{IRQ4}_57") (pintype "bidirectional"))
      (node (ref "3") (pin "57") (pinfunction "~{IRQ4}_57") (pintype "bidirectional"))
      (node (ref "4") (pin "52") (pinfunction "~{IRQX}_52") (pintype "bidirectional"))
      (node (ref "4") (pin "57") (pinfunction "~{IRQ4}_57") (pintype "bidirectional"))
      (node (ref "5") (pin "57") (pinfunction "~{IRQ4}_57") (pintype "bidirectional"))
      (node (ref "6") (pin "57") (pinfunction "~{IRQ4}_57") (pintype "bidirectional"))
      (node (ref "7") (pin "57") (pinfunction "~{IRQ4}_57") (pintype "bidirectional"))
      (node (ref "RN3") (pin "4") (pinfunction "4_4") (pintype "passive"))
      (node (ref "RN9") (pin "4") (pinfunction "4_4") (pintype "passive"))
    )
    (net (code "119") (name "~{IRQ5}") (class "Default")
      (node (ref "0") (pin "58") (pinfunction "~{IRQ5}_58") (pintype "bidirectional"))
      (node (ref "1") (pin "58") (pinfunction "~{IRQ5}_58") (pintype "bidirectional"))
      (node (ref "2") (pin "58") (pinfunction "~{IRQ5}_58") (pintype "bidirectional"))
      (node (ref "3") (pin "58") (pinfunction "~{IRQ5}_58") (pintype "bidirectional"))
      (node (ref "4") (pin "58") (pinfunction "~{IRQ5}_58") (pintype "bidirectional"))
      (node (ref "5") (pin "52") (pinfunction "~{IRQX}_52") (pintype "bidirectional"))
      (node (ref "5") (pin "58") (pinfunction "~{IRQ5}_58") (pintype "bidirectional"))
      (node (ref "6") (pin "58") (pinfunction "~{IRQ5}_58") (pintype "bidirectional"))
      (node (ref "7") (pin "58") (pinfunction "~{IRQ5}_58") (pintype "bidirectional"))
      (node (ref "RN12") (pin "3") (pinfunction "3_3") (pintype "passive"))
      (node (ref "RN6") (pin "3") (pinfunction "3_3") (pintype "passive"))
    )
    (net (code "120") (name "~{IRQ6}") (class "Default")
      (node (ref "0") (pin "59") (pinfunction "~{IRQ6}_59") (pintype "bidirectional"))
      (node (ref "1") (pin "59") (pinfunction "~{IRQ6}_59") (pintype "bidirectional"))
      (node (ref "2") (pin "59") (pinfunction "~{IRQ6}_59") (pintype "bidirectional"))
      (node (ref "3") (pin "59") (pinfunction "~{IRQ6}_59") (pintype "bidirectional"))
      (node (ref "4") (pin "59") (pinfunction "~{IRQ6}_59") (pintype "bidirectional"))
      (node (ref "5") (pin "59") (pinfunction "~{IRQ6}_59") (pintype "bidirectional"))
      (node (ref "6") (pin "52") (pinfunction "~{IRQX}_52") (pintype "bidirectional"))
      (node (ref "6") (pin "59") (pinfunction "~{IRQ6}_59") (pintype "bidirectional"))
      (node (ref "7") (pin "59") (pinfunction "~{IRQ6}_59") (pintype "bidirectional"))
      (node (ref "RN3") (pin "3") (pinfunction "3_3") (pintype "passive"))
      (node (ref "RN9") (pin "3") (pinfunction "3_3") (pintype "passive"))
    )
    (net (code "121") (name "~{IRQ7}") (class "Default")
      (node (ref "0") (pin "60") (pinfunction "~{IRQ7}_60") (pintype "bidirectional"))
      (node (ref "1") (pin "60") (pinfunction "~{IRQ7}_60") (pintype "bidirectional"))
      (node (ref "2") (pin "60") (pinfunction "~{IRQ7}_60") (pintype "bidirectional"))
      (node (ref "3") (pin "60") (pinfunction "~{IRQ7}_60") (pintype "bidirectional"))
      (node (ref "4") (pin "60") (pinfunction "~{IRQ7}_60") (pintype "bidirectional"))
      (node (ref "5") (pin "60") (pinfunction "~{IRQ7}_60") (pintype "bidirectional"))
      (node (ref "6") (pin "60") (pinfunction "~{IRQ7}_60") (pintype "bidirectional"))
      (node (ref "7") (pin "52") (pinfunction "~{IRQX}_52") (pintype "bidirectional"))
      (node (ref "7") (pin "60") (pinfunction "~{IRQ7}_60") (pintype "bidirectional"))
      (node (ref "RN12") (pin "2") (pinfunction "2_2") (pintype "passive"))
      (node (ref "RN6") (pin "2") (pinfunction "2_2") (pintype "passive"))
    )
    (net (code "122") (name "~{NMI}") (class "Default")
      (node (ref "0") (pin "61") (pinfunction "~{NMI}_61") (pintype "bidirectional"))
      (node (ref "1") (pin "61") (pinfunction "~{NMI}_61") (pintype "bidirectional"))
      (node (ref "2") (pin "61") (pinfunction "~{NMI}_61") (pintype "bidirectional"))
      (node (ref "3") (pin "61") (pinfunction "~{NMI}_61") (pintype "bidirectional"))
      (node (ref "4") (pin "61") (pinfunction "~{NMI}_61") (pintype "bidirectional"))
      (node (ref "5") (pin "61") (pinfunction "~{NMI}_61") (pintype "bidirectional"))
      (node (ref "6") (pin "61") (pinfunction "~{NMI}_61") (pintype "bidirectional"))
      (node (ref "7") (pin "61") (pinfunction "~{NMI}_61") (pintype "bidirectional"))
      (node (ref "RN3") (pin "2") (pinfunction "2_2") (pintype "passive"))
      (node (ref "RN9") (pin "2") (pinfunction "2_2") (pintype "passive"))
    )
    (net (code "123") (name "~{RD}") (class "Default")
      (node (ref "0") (pin "21") (pinfunction "~{RD}_21") (pintype "bidirectional"))
      (node (ref "1") (pin "21") (pinfunction "~{RD}_21") (pintype "bidirectional"))
      (node (ref "2") (pin "21") (pinfunction "~{RD}_21") (pintype "bidirectional"))
      (node (ref "3") (pin "21") (pinfunction "~{RD}_21") (pintype "bidirectional"))
      (node (ref "4") (pin "21") (pinfunction "~{RD}_21") (pintype "bidirectional"))
      (node (ref "5") (pin "21") (pinfunction "~{RD}_21") (pintype "bidirectional"))
      (node (ref "6") (pin "21") (pinfunction "~{RD}_21") (pintype "bidirectional"))
      (node (ref "7") (pin "21") (pinfunction "~{RD}_21") (pintype "bidirectional"))
      (node (ref "RN10") (pin "6") (pinfunction "6_6") (pintype "passive"))
      (node (ref "RN4") (pin "6") (pinfunction "6_6") (pintype "passive"))
    )
    (net (code "124") (name "~{RST}") (class "Default")
      (node (ref "0") (pin "14") (pinfunction "~{RST}_14") (pintype "bidirectional"))
      (node (ref "1") (pin "14") (pinfunction "~{RST}_14") (pintype "bidirectional"))
      (node (ref "2") (pin "14") (pinfunction "~{RST}_14") (pintype "bidirectional"))
      (node (ref "3") (pin "14") (pinfunction "~{RST}_14") (pintype "bidirectional"))
      (node (ref "4") (pin "14") (pinfunction "~{RST}_14") (pintype "bidirectional"))
      (node (ref "5") (pin "14") (pinfunction "~{RST}_14") (pintype "bidirectional"))
      (node (ref "6") (pin "14") (pinfunction "~{RST}_14") (pintype "bidirectional"))
      (node (ref "7") (pin "14") (pinfunction "~{RST}_14") (pintype "bidirectional"))
      (node (ref "JP7") (pin "2") (pinfunction "2_2") (pintype "passive"))
      (node (ref "R10") (pin "1") (pinfunction "1_1") (pintype "passive"))
      (node (ref "RN1") (pin "2") (pinfunction "2_2") (pintype "passive"))
      (node (ref "RN7") (pin "2") (pinfunction "2_2") (pintype "passive"))
    )
    (net (code "125") (name "~{WAIT}") (class "Default")
      (node (ref "0") (pin "18") (pinfunction "~{WAIT}_18") (pintype "bidirectional"))
      (node (ref "1") (pin "18") (pinfunction "~{WAIT}_18") (pintype "bidirectional"))
      (node (ref "2") (pin "18") (pinfunction "~{WAIT}_18") (pintype "bidirectional"))
      (node (ref "3") (pin "18") (pinfunction "~{WAIT}_18") (pintype "bidirectional"))
      (node (ref "4") (pin "18") (pinfunction "~{WAIT}_18") (pintype "bidirectional"))
      (node (ref "5") (pin "18") (pinfunction "~{WAIT}_18") (pintype "bidirectional"))
      (node (ref "6") (pin "18") (pinfunction "~{WAIT}_18") (pintype "bidirectional"))
      (node (ref "7") (pin "18") (pinfunction "~{WAIT}_18") (pintype "bidirectional"))
      (node (ref "RN1") (pin "4") (pinfunction "4_4") (pintype "passive"))
      (node (ref "RN7") (pin "4") (pinfunction "4_4") (pintype "passive"))
    )
    (net (code "126") (name "~{WR}") (class "Default")
      (node (ref "0") (pin "22") (pinfunction "~{WR}_22") (pintype "bidirectional"))
      (node (ref "1") (pin "22") (pinfunction "~{WR}_22") (pintype "bidirectional"))
      (node (ref "2") (pin "22") (pinfunction "~{WR}_22") (pintype "bidirectional"))
      (node (ref "3") (pin "22") (pinfunction "~{WR}_22") (pintype "bidirectional"))
      (node (ref "4") (pin "22") (pinfunction "~{WR}_22") (pintype "bidirectional"))
      (node (ref "5") (pin "22") (pinfunction "~{WR}_22") (pintype "bidirectional"))
      (node (ref "6") (pin "22") (pinfunction "~{WR}_22") (pintype "bidirectional"))
      (node (ref "7") (pin "22") (pinfunction "~{WR}_22") (pintype "bidirectional"))
      (node (ref "RN1") (pin "6") (pinfunction "6_6") (pintype "passive"))
      (node (ref "RN7") (pin "6") (pinfunction "6_6") (pintype "passive"))
    )
  )
)
